# dio-pci.net
KiCad netlist of a schematic drawn in EAGLE
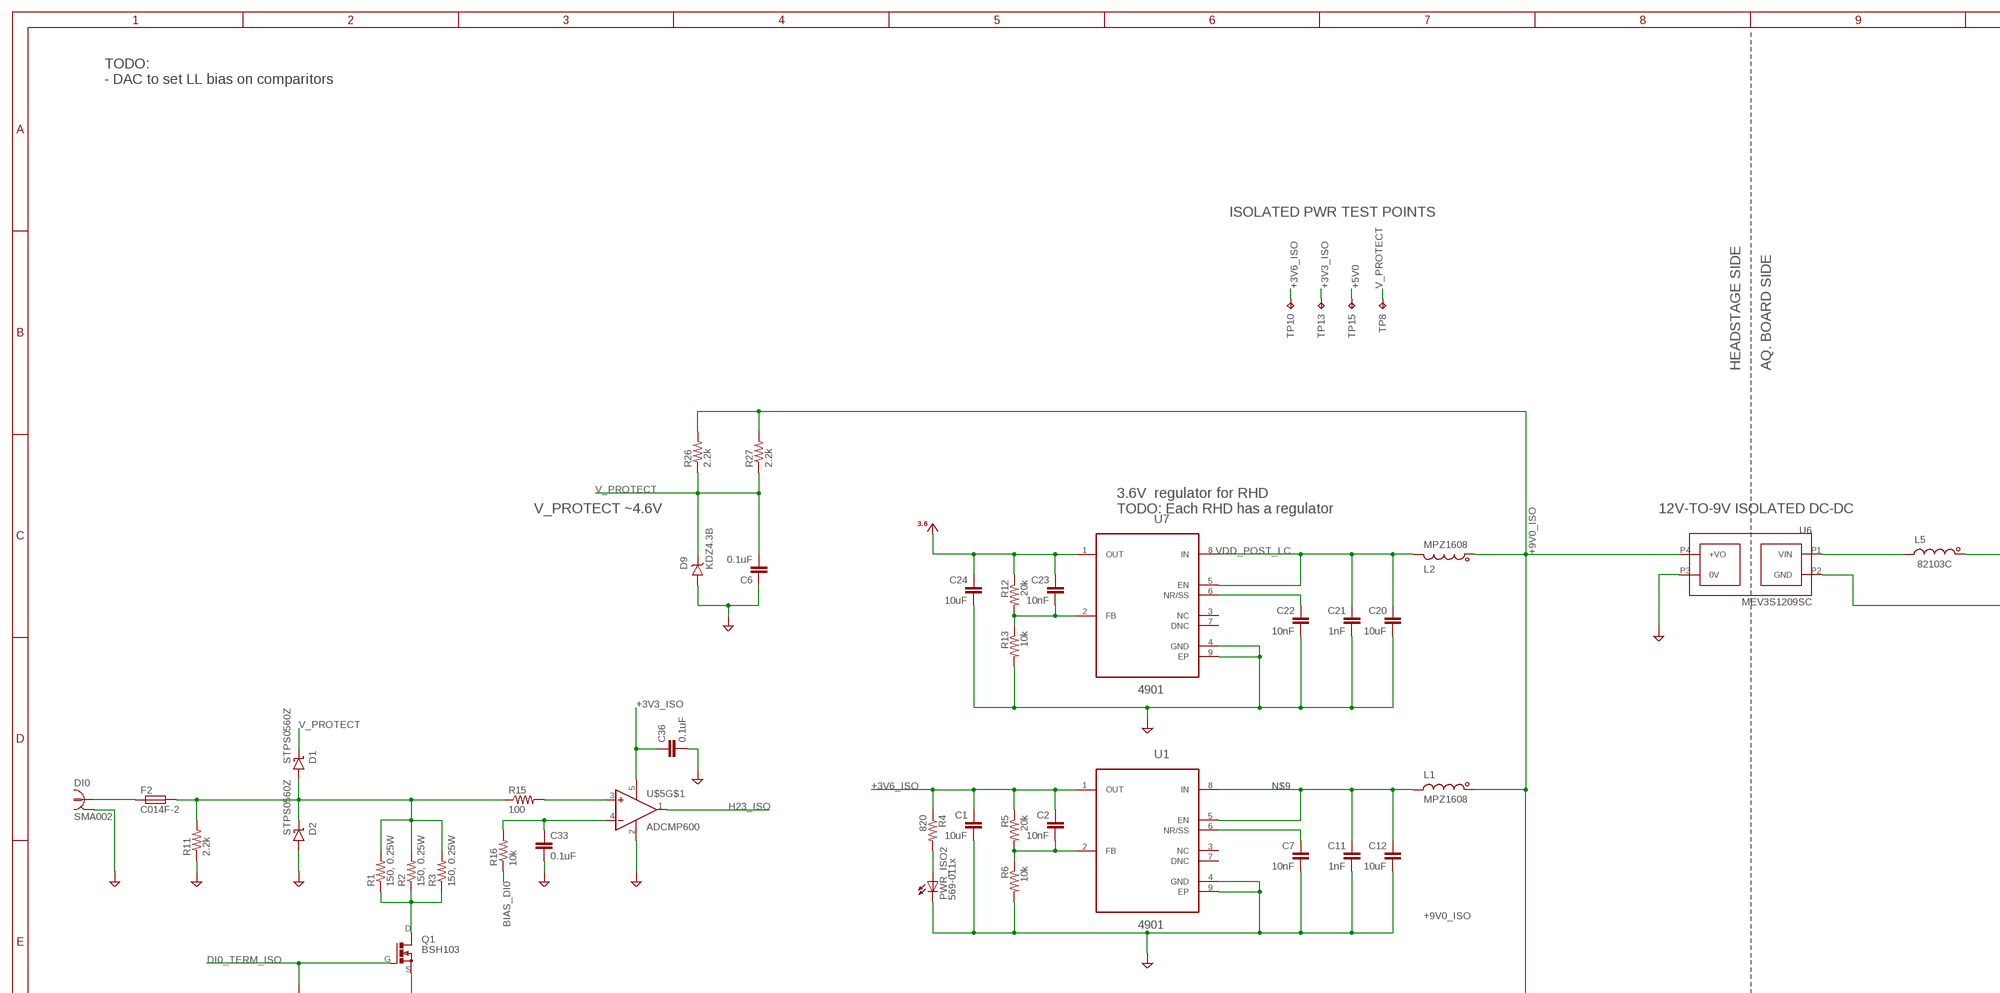
[diagram p0: schematic, sheet 1, part 1 of 3]
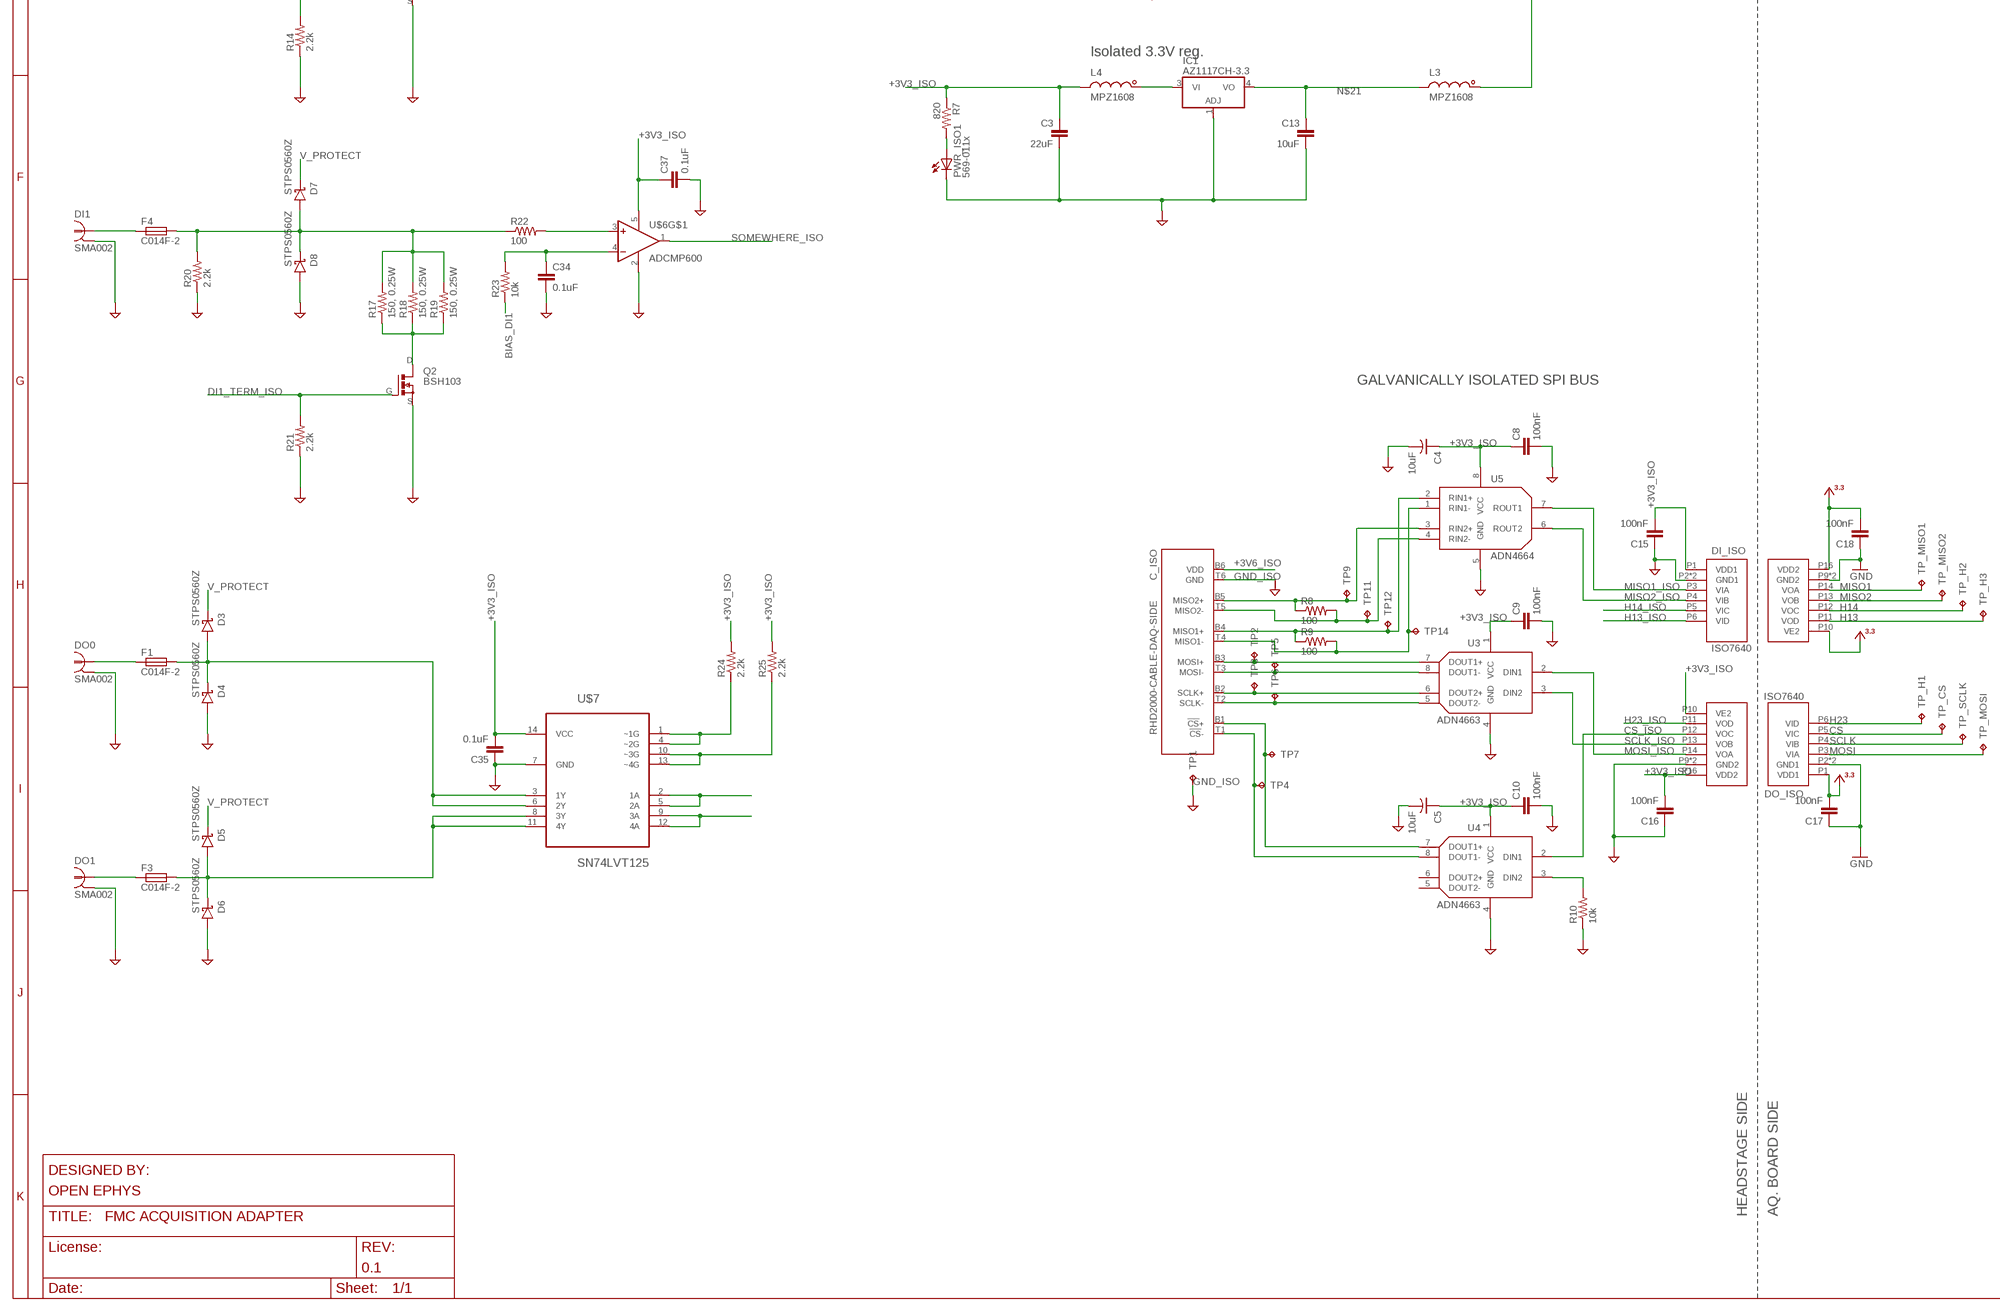
[diagram p1: schematic, sheet 1, part 2 of 3]
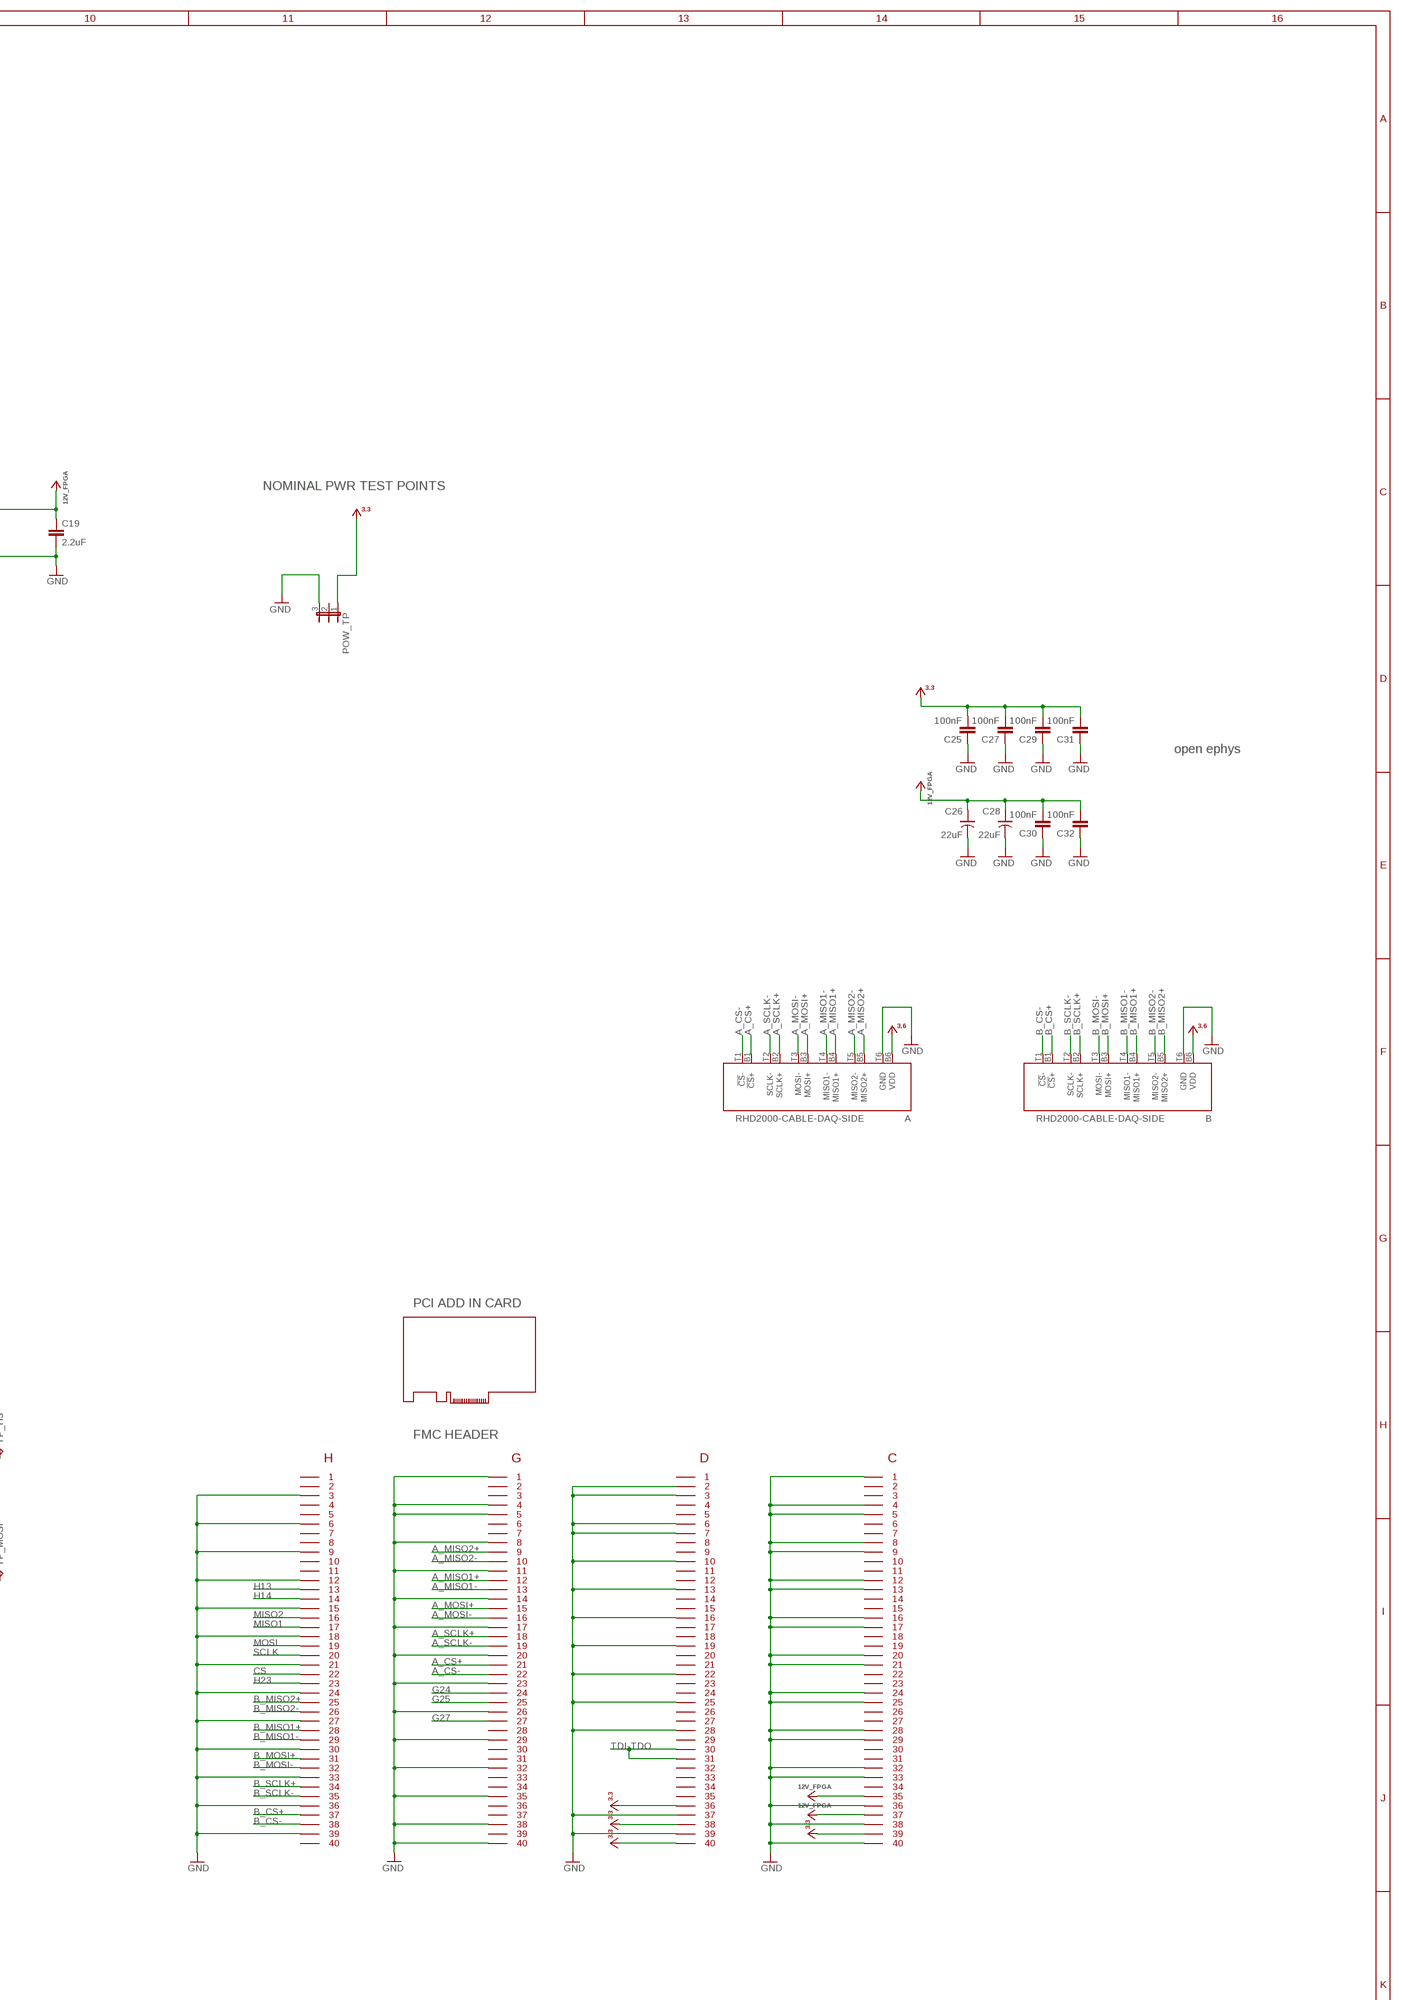
[diagram p2: schematic, sheet 1, part 3 of 3]

(export (version "E")
  (design (tool "Eeschema 10.0.6"))
  (components
    (comp (ref "A")
      (value "RHD2000-CABLE-DAQ-SIDE")
      (footprint "eagle-import:OMNETICS_PZN-12-AA")
      (libsource (lib "eagle-import") (part "RHD2000-CABLE-DAQ-SIDE"))
    )
    (comp (ref "B")
      (value "RHD2000-CABLE-DAQ-SIDE")
      (footprint "eagle-import:OMNETICS_PZN-12-AA")
      (libsource (lib "eagle-import") (part "RHD2000-CABLE-DAQ-SIDE"))
    )
    (comp (ref "C1")
      (value "10uF")
      (footprint "eagle-import:1206")
      (libsource (lib "eagle-import") (part "puggleboard_C_1206"))
    )
    (comp (ref "C2")
      (value "10nF")
      (footprint "eagle-import:0603")
      (libsource (lib "eagle-import") (part "jonnew_C_0603"))
    )
    (comp (ref "C3")
      (value "22uF")
      (footprint "eagle-import:1206")
      (libsource (lib "eagle-import") (part "C_1206"))
    )
    (comp (ref "C4")
      (value "10uF")
      (footprint "eagle-import:1206-POL")
      (libsource (lib "eagle-import") (part "C-POL_1206"))
    )
    (comp (ref "C5")
      (value "10uF")
      (footprint "eagle-import:1206-POL")
      (libsource (lib "eagle-import") (part "C-POL_1206"))
    )
    (comp (ref "C6")
      (value "0.1uF")
      (footprint "eagle-import:0603")
      (libsource (lib "eagle-import") (part "jonnew_C_0603"))
    )
    (comp (ref "C7")
      (value "10nF")
      (footprint "eagle-import:0603")
      (libsource (lib "eagle-import") (part "jonnew_C_0603"))
    )
    (comp (ref "C8")
      (value "100nF")
      (footprint "eagle-import:0603")
      (libsource (lib "eagle-import") (part "C_0603"))
    )
    (comp (ref "C9")
      (value "100nF")
      (footprint "eagle-import:0603")
      (libsource (lib "eagle-import") (part "C_0603"))
    )
    (comp (ref "C10")
      (value "100nF")
      (footprint "eagle-import:0603")
      (libsource (lib "eagle-import") (part "C_0603"))
    )
    (comp (ref "C11")
      (value "1nF")
      (footprint "eagle-import:0603")
      (libsource (lib "eagle-import") (part "jonnew_C_0603"))
    )
    (comp (ref "C12")
      (value "10uF")
      (footprint "eagle-import:1206")
      (libsource (lib "eagle-import") (part "puggleboard_C_1206"))
    )
    (comp (ref "C13")
      (value "10uF")
      (footprint "eagle-import:1206")
      (libsource (lib "eagle-import") (part "jonnew_C_1206"))
    )
    (comp (ref "C15")
      (value "100nF")
      (footprint "eagle-import:0603")
      (libsource (lib "eagle-import") (part "C_0603"))
    )
    (comp (ref "C16")
      (value "100nF")
      (footprint "eagle-import:0603")
      (libsource (lib "eagle-import") (part "C_0603"))
    )
    (comp (ref "C17")
      (value "100nF")
      (footprint "eagle-import:0603")
      (libsource (lib "eagle-import") (part "C_0603"))
    )
    (comp (ref "C18")
      (value "100nF")
      (footprint "eagle-import:0603")
      (libsource (lib "eagle-import") (part "C_0603"))
    )
    (comp (ref "C19")
      (value "2.2uF")
      (footprint "eagle-import:1206")
      (libsource (lib "eagle-import") (part "jonnew_C_1206"))
    )
    (comp (ref "C20")
      (value "10uF")
      (footprint "eagle-import:1206")
      (libsource (lib "eagle-import") (part "puggleboard_C_1206"))
    )
    (comp (ref "C21")
      (value "1nF")
      (footprint "eagle-import:0603")
      (libsource (lib "eagle-import") (part "jonnew_C_0603"))
    )
    (comp (ref "C22")
      (value "10nF")
      (footprint "eagle-import:0603")
      (libsource (lib "eagle-import") (part "jonnew_C_0603"))
    )
    (comp (ref "C23")
      (value "10nF")
      (footprint "eagle-import:0603")
      (libsource (lib "eagle-import") (part "jonnew_C_0603"))
    )
    (comp (ref "C24")
      (value "10uF")
      (footprint "eagle-import:1206")
      (libsource (lib "eagle-import") (part "puggleboard_C_1206"))
    )
    (comp (ref "C25")
      (value "100nF")
      (footprint "eagle-import:0603")
      (libsource (lib "eagle-import") (part "C_0603"))
    )
    (comp (ref "C26")
      (value "22uF")
      (footprint "eagle-import:1210-POL")
      (libsource (lib "eagle-import") (part "C-POL_1210"))
    )
    (comp (ref "C27")
      (value "100nF")
      (footprint "eagle-import:0603")
      (libsource (lib "eagle-import") (part "C_0603"))
    )
    (comp (ref "C28")
      (value "22uF")
      (footprint "eagle-import:1210-POL")
      (libsource (lib "eagle-import") (part "C-POL_1210"))
    )
    (comp (ref "C29")
      (value "100nF")
      (footprint "eagle-import:0603")
      (libsource (lib "eagle-import") (part "C_0603"))
    )
    (comp (ref "C30")
      (value "100nF")
      (footprint "eagle-import:0603")
      (libsource (lib "eagle-import") (part "C_0603"))
    )
    (comp (ref "C31")
      (value "100nF")
      (footprint "eagle-import:0603")
      (libsource (lib "eagle-import") (part "C_0603"))
    )
    (comp (ref "C32")
      (value "100nF")
      (footprint "eagle-import:0603")
      (libsource (lib "eagle-import") (part "C_0603"))
    )
    (comp (ref "C33")
      (value "0.1uF")
      (footprint "eagle-import:0603")
      (libsource (lib "eagle-import") (part "jonnew_C_0603"))
    )
    (comp (ref "C34")
      (value "0.1uF")
      (footprint "eagle-import:0603")
      (libsource (lib "eagle-import") (part "jonnew_C_0603"))
    )
    (comp (ref "C35")
      (value "0.1uF")
      (footprint "eagle-import:0603")
      (libsource (lib "eagle-import") (part "C_0603"))
    )
    (comp (ref "C36")
      (value "0.1uF")
      (footprint "eagle-import:0603")
      (libsource (lib "eagle-import") (part "jonnew_C_0603"))
    )
    (comp (ref "C37")
      (value "0.1uF")
      (footprint "eagle-import:0603")
      (libsource (lib "eagle-import") (part "jonnew_C_0603"))
    )
    (comp (ref "C_ISO")
      (value "RHD2000-CABLE-DAQ-SIDE")
      (footprint "eagle-import:OMNETICS_PZN-12-AA")
      (libsource (lib "eagle-import") (part "RHD2000-CABLE-DAQ-SIDE"))
    )
    (comp (ref "D1")
      (value "STPS0560Z")
      (footprint "eagle-import:SOD123")
      (libsource (lib "eagle-import") (part "S-DIODESOD-123"))
    )
    (comp (ref "D2")
      (value "STPS0560Z")
      (footprint "eagle-import:SOD123")
      (libsource (lib "eagle-import") (part "S-DIODESOD-123"))
    )
    (comp (ref "D3")
      (value "STPS0560Z")
      (footprint "eagle-import:SOD123")
      (libsource (lib "eagle-import") (part "S-DIODESOD-123"))
    )
    (comp (ref "D4")
      (value "STPS0560Z")
      (footprint "eagle-import:SOD123")
      (libsource (lib "eagle-import") (part "S-DIODESOD-123"))
    )
    (comp (ref "D5")
      (value "STPS0560Z")
      (footprint "eagle-import:SOD123")
      (libsource (lib "eagle-import") (part "S-DIODESOD-123"))
    )
    (comp (ref "D6")
      (value "STPS0560Z")
      (footprint "eagle-import:SOD123")
      (libsource (lib "eagle-import") (part "S-DIODESOD-123"))
    )
    (comp (ref "D7")
      (value "STPS0560Z")
      (footprint "eagle-import:SOD123")
      (libsource (lib "eagle-import") (part "S-DIODESOD-123"))
    )
    (comp (ref "D8")
      (value "STPS0560Z")
      (footprint "eagle-import:SOD123")
      (libsource (lib "eagle-import") (part "S-DIODESOD-123"))
    )
    (comp (ref "D9")
      (value "KDZ4.3B")
      (footprint "eagle-import:SOD123")
      (libsource (lib "eagle-import") (part "Z-DIODE_SOD123"))
    )
    (comp (ref "DI0")
      (value "SMA002")
      (footprint "eagle-import:SMA_JACK_CONREVSMA002-G")
      (libsource (lib "eagle-import") (part "COAX_CONREVSMA002-G"))
    )
    (comp (ref "DI1")
      (value "SMA002")
      (footprint "eagle-import:SMA_JACK_CONREVSMA002-G")
      (libsource (lib "eagle-import") (part "COAX_CONREVSMA002-G"))
    )
    (comp (ref "DI_ISO")
      (value "ISO7640")
      (footprint "eagle-import:SOIC_WIDE_16")
      (libsource (lib "eagle-import") (part "ADUM3440"))
    )
    (comp (ref "DO0")
      (value "SMA002")
      (footprint "eagle-import:SMA_JACK_CONREVSMA002-G")
      (libsource (lib "eagle-import") (part "COAX_CONREVSMA002-G"))
    )
    (comp (ref "DO1")
      (value "SMA002")
      (footprint "eagle-import:SMA_JACK_CONREVSMA002-G")
      (libsource (lib "eagle-import") (part "COAX_CONREVSMA002-G"))
    )
    (comp (ref "DO_ISO")
      (value "ISO7640")
      (footprint "eagle-import:SOIC_WIDE_16")
      (libsource (lib "eagle-import") (part "ADUM3440"))
    )
    (comp (ref "F1")
      (value "C014F-2")
      (footprint "eagle-import:1812")
      (libsource (lib "eagle-import") (part "FUSE_1812"))
    )
    (comp (ref "F2")
      (value "C014F-2")
      (footprint "eagle-import:1812")
      (libsource (lib "eagle-import") (part "FUSE_1812"))
    )
    (comp (ref "F3")
      (value "C014F-2")
      (footprint "eagle-import:1812")
      (libsource (lib "eagle-import") (part "FUSE_1812"))
    )
    (comp (ref "F4")
      (value "C014F-2")
      (footprint "eagle-import:1812")
      (libsource (lib "eagle-import") (part "FUSE_1812"))
    )
    (comp (ref "FMC")
      (value "FMC_LPC_160_PIN")
      (footprint "eagle-import:FMC_LPC_MALE_WITH_SP601_BSILK")
      (libsource (lib "eagle-import") (part "FMC_LPC_160_PIN"))
    )
    (comp (ref "IC1")
      (value "AZ1117CH-3.3")
      (footprint "eagle-import:SOT223")
      (libsource (lib "eagle-import") (part "317EMP"))
    )
    (comp (ref "L1")
      (value "MPZ1608")
      (footprint "eagle-import:0603")
      (libsource (lib "eagle-import") (part "L_0603"))
    )
    (comp (ref "L2")
      (value "MPZ1608")
      (footprint "eagle-import:0603")
      (libsource (lib "eagle-import") (part "L_0603"))
    )
    (comp (ref "L3")
      (value "MPZ1608")
      (footprint "eagle-import:0603")
      (libsource (lib "eagle-import") (part "L_0603"))
    )
    (comp (ref "L4")
      (value "MPZ1608")
      (footprint "eagle-import:0603")
      (libsource (lib "eagle-import") (part "L_0603"))
    )
    (comp (ref "L5")
      (value "82103C")
      (footprint "eagle-import:1210")
      (libsource (lib "eagle-import") (part "L_1210"))
    )
    (comp (ref "POW_TP")
      (value "JP3E")
      (footprint "eagle-import:JP3")
      (libsource (lib "eagle-import") (part "JP3E"))
    )
    (comp (ref "PWR_ISO")
      (value "569-011x")
      (footprint "eagle-import:569-011X-X00_LED_ARRAY")
      (libsource (lib "eagle-import") (part "LED_2X_VERTICAL"))
    )
    (comp (ref "Q1")
      (value "BSH103")
      (footprint "eagle-import:SOT23-GSD")
      (libsource (lib "eagle-import") (part "N-MOSFET_SOT23-GSD"))
    )
    (comp (ref "Q2")
      (value "BSH103")
      (footprint "eagle-import:SOT23-GSD")
      (libsource (lib "eagle-import") (part "N-MOSFET_SOT23-GSD"))
    )
    (comp (ref "R1")
      (value "150, 0.25W")
      (footprint "eagle-import:1206")
      (libsource (lib "eagle-import") (part "jonnew_R_1206"))
    )
    (comp (ref "R2")
      (value "150, 0.25W")
      (footprint "eagle-import:1206")
      (libsource (lib "eagle-import") (part "jonnew_R_1206"))
    )
    (comp (ref "R3")
      (value "150, 0.25W")
      (footprint "eagle-import:1206")
      (libsource (lib "eagle-import") (part "jonnew_R_1206"))
    )
    (comp (ref "R4")
      (value "820")
      (footprint "eagle-import:0603")
      (libsource (lib "eagle-import") (part "R_0603"))
    )
    (comp (ref "R5")
      (value "20k")
      (footprint "eagle-import:0603")
      (fields (field (name "MPN") "ERJ-3EKFxxxxV"))
      (libsource (lib "eagle-import") (part "jonnew_R_0603"))
    )
    (comp (ref "R6")
      (value "10k")
      (footprint "eagle-import:0603")
      (fields (field (name "MPN") "ERJ-3EKFxxxxV"))
      (libsource (lib "eagle-import") (part "jonnew_R_0603"))
    )
    (comp (ref "R7")
      (value "820")
      (footprint "eagle-import:0603")
      (libsource (lib "eagle-import") (part "R_0603"))
    )
    (comp (ref "R8")
      (value "100")
      (footprint "eagle-import:0603")
      (libsource (lib "eagle-import") (part "R_0603"))
    )
    (comp (ref "R9")
      (value "100")
      (footprint "eagle-import:0603")
      (libsource (lib "eagle-import") (part "R_0603"))
    )
    (comp (ref "R10")
      (value "10k")
      (footprint "eagle-import:0603")
      (fields (field (name "MPN") "ERJ-3EKFxxxxV"))
      (libsource (lib "eagle-import") (part "jonnew_R_0603"))
    )
    (comp (ref "R11")
      (value "2.2k")
      (footprint "eagle-import:0603")
      (fields (field (name "MPN") "ERJ-3EKFxxxxV"))
      (libsource (lib "eagle-import") (part "jonnew_R_0603"))
    )
    (comp (ref "R12")
      (value "20k")
      (footprint "eagle-import:0603")
      (fields (field (name "MPN") "ERJ-3EKFxxxxV"))
      (libsource (lib "eagle-import") (part "jonnew_R_0603"))
    )
    (comp (ref "R13")
      (value "10k")
      (footprint "eagle-import:0603")
      (fields (field (name "MPN") "ERJ-3EKFxxxxV"))
      (libsource (lib "eagle-import") (part "jonnew_R_0603"))
    )
    (comp (ref "R14")
      (value "2.2k")
      (footprint "eagle-import:0603")
      (fields (field (name "MPN") "ERJ-3EKFxxxxV"))
      (libsource (lib "eagle-import") (part "jonnew_R_0603"))
    )
    (comp (ref "R15")
      (value "100")
      (footprint "eagle-import:0603")
      (fields (field (name "MPN") "ERJ-3EKFxxxxV"))
      (libsource (lib "eagle-import") (part "jonnew_R_0603"))
    )
    (comp (ref "R16")
      (value "10k")
      (footprint "eagle-import:0603")
      (fields (field (name "MPN") "ERJ-3EKFxxxxV"))
      (libsource (lib "eagle-import") (part "jonnew_R_0603"))
    )
    (comp (ref "R17")
      (value "150, 0.25W")
      (footprint "eagle-import:1206")
      (libsource (lib "eagle-import") (part "jonnew_R_1206"))
    )
    (comp (ref "R18")
      (value "150, 0.25W")
      (footprint "eagle-import:1206")
      (libsource (lib "eagle-import") (part "jonnew_R_1206"))
    )
    (comp (ref "R19")
      (value "150, 0.25W")
      (footprint "eagle-import:1206")
      (libsource (lib "eagle-import") (part "jonnew_R_1206"))
    )
    (comp (ref "R20")
      (value "2.2k")
      (footprint "eagle-import:0603")
      (fields (field (name "MPN") "ERJ-3EKFxxxxV"))
      (libsource (lib "eagle-import") (part "jonnew_R_0603"))
    )
    (comp (ref "R21")
      (value "2.2k")
      (footprint "eagle-import:0603")
      (fields (field (name "MPN") "ERJ-3EKFxxxxV"))
      (libsource (lib "eagle-import") (part "jonnew_R_0603"))
    )
    (comp (ref "R22")
      (value "100")
      (footprint "eagle-import:0603")
      (fields (field (name "MPN") "ERJ-3EKFxxxxV"))
      (libsource (lib "eagle-import") (part "jonnew_R_0603"))
    )
    (comp (ref "R23")
      (value "10k")
      (footprint "eagle-import:0603")
      (fields (field (name "MPN") "ERJ-3EKFxxxxV"))
      (libsource (lib "eagle-import") (part "jonnew_R_0603"))
    )
    (comp (ref "R24")
      (value "2.2k")
      (footprint "eagle-import:0603")
      (fields (field (name "MPN") "ERJ-3EKFxxxxV"))
      (libsource (lib "eagle-import") (part "jonnew_R_0603"))
    )
    (comp (ref "R25")
      (value "2.2k")
      (footprint "eagle-import:0603")
      (fields (field (name "MPN") "ERJ-3EKFxxxxV"))
      (libsource (lib "eagle-import") (part "jonnew_R_0603"))
    )
    (comp (ref "R26")
      (value "2.2k")
      (footprint "eagle-import:0603")
      (fields (field (name "MPN") "ERJ-3EKFxxxxV"))
      (libsource (lib "eagle-import") (part "jonnew_R_0603"))
    )
    (comp (ref "R27")
      (value "2.2k")
      (footprint "eagle-import:0603")
      (fields (field (name "MPN") "ERJ-3EKFxxxxV"))
      (libsource (lib "eagle-import") (part "jonnew_R_0603"))
    )
    (comp (ref "TP1")
      (value "GND-ISO")
      (footprint "eagle-import:P1-13")
      (libsource (lib "eagle-import") (part "TPPAD1-13"))
    )
    (comp (ref "TP2")
      (value "MOSI+")
      (footprint "eagle-import:TP06R")
      (libsource (lib "eagle-import") (part "TPTP06R"))
    )
    (comp (ref "TP3")
      (value "SCLK+")
      (footprint "eagle-import:TP06R")
      (libsource (lib "eagle-import") (part "TPTP06R"))
    )
    (comp (ref "TP4")
      (value "CS-")
      (footprint "eagle-import:TP06R")
      (libsource (lib "eagle-import") (part "TPTP06R"))
    )
    (comp (ref "TP5")
      (value "MOSI-")
      (footprint "eagle-import:TP06R")
      (libsource (lib "eagle-import") (part "TPTP06R"))
    )
    (comp (ref "TP6")
      (value "SCLK-")
      (footprint "eagle-import:TP06R")
      (libsource (lib "eagle-import") (part "TPTP06R"))
    )
    (comp (ref "TP7")
      (value "CS+")
      (footprint "eagle-import:TP06R")
      (libsource (lib "eagle-import") (part "TPTP06R"))
    )
    (comp (ref "TP8")
      (value "+5V0")
      (footprint "eagle-import:TP06R")
      (libsource (lib "eagle-import") (part "TPTP06R"))
    )
    (comp (ref "TP9")
      (value "MISO2+")
      (footprint "eagle-import:TP06R")
      (libsource (lib "eagle-import") (part "TPTP06R"))
    )
    (comp (ref "TP10")
      (value "+3V6")
      (footprint "eagle-import:TP06R")
      (libsource (lib "eagle-import") (part "TPTP06R"))
    )
    (comp (ref "TP11")
      (value "MISO2-")
      (footprint "eagle-import:TP06R")
      (libsource (lib "eagle-import") (part "TPTP06R"))
    )
    (comp (ref "TP12")
      (value "MISO1+")
      (footprint "eagle-import:TP06R")
      (libsource (lib "eagle-import") (part "TPTP06R"))
    )
    (comp (ref "TP13")
      (value "+3V3")
      (footprint "eagle-import:TP06R")
      (libsource (lib "eagle-import") (part "TPTP06R"))
    )
    (comp (ref "TP14")
      (value "MISO1-")
      (footprint "eagle-import:TP06R")
      (libsource (lib "eagle-import") (part "TPTP06R"))
    )
    (comp (ref "TP15")
      (value "+5V0")
      (footprint "eagle-import:TP06R")
      (libsource (lib "eagle-import") (part "TPTP06R"))
    )
    (comp (ref "TP_CS")
      (value "CS")
      (footprint "eagle-import:TP06R")
      (libsource (lib "eagle-import") (part "TPTP06R"))
    )
    (comp (ref "TP_H1")
      (value "H23")
      (footprint "eagle-import:TP06R")
      (libsource (lib "eagle-import") (part "TPTP06R"))
    )
    (comp (ref "TP_H2")
      (value "H14")
      (footprint "eagle-import:TP06R")
      (libsource (lib "eagle-import") (part "TPTP06R"))
    )
    (comp (ref "TP_H3")
      (value "H13")
      (footprint "eagle-import:TP06R")
      (libsource (lib "eagle-import") (part "TPTP06R"))
    )
    (comp (ref "TP_MISO1")
      (value "MISO1")
      (footprint "eagle-import:TP06R")
      (libsource (lib "eagle-import") (part "TPTP06R"))
    )
    (comp (ref "TP_MISO2")
      (value "MISO2")
      (footprint "eagle-import:TP06R")
      (libsource (lib "eagle-import") (part "TPTP06R"))
    )
    (comp (ref "TP_MOSI")
      (value "MOSI")
      (footprint "eagle-import:TP06R")
      (libsource (lib "eagle-import") (part "TPTP06R"))
    )
    (comp (ref "TP_SCLK")
      (value "SCLK")
      (footprint "eagle-import:TP06R")
      (libsource (lib "eagle-import") (part "TPTP06R"))
    )
    (comp (ref "U$1")
      (value "OPEN_EPHYS_LOGO")
      (footprint "eagle-import:OPEN_EPHYS_LOGO")
      (libsource (lib "eagle-import") (part "OPEN_EPHYS_LOGO"))
    )
    (comp (ref "U$2")
      (value "PCI-MECH_STD-H_HALF-W")
      (footprint "eagle-import:PCI-ADDIN_STD-H_HALF-L")
      (libsource (lib "eagle-import") (part "PCI-MECH_STD-H_HALF-W"))
    )
    (comp (ref "U$5")
      (value "ADCMP600")
      (footprint "eagle-import:SOT-23-5")
      (libsource (lib "eagle-import") (part "COMPARITOR_ADCMP600"))
    )
    (comp (ref "U$6")
      (value "ADCMP600")
      (footprint "eagle-import:SOT-23-5")
      (libsource (lib "eagle-import") (part "COMPARITOR_ADCMP600"))
    )
    (comp (ref "U$7")
      (value "SN74LVT125")
      (footprint "eagle-import:SO14")
      (libsource (lib "eagle-import") (part "QUAD-LINE-DRIVER_SOIC"))
    )
    (comp (ref "U1")
      (value "4901")
      (footprint "eagle-import:SOP65P490X110-9N")
      (fields (field (name "MPN") "TPS7A4901DGNR"))
      (libsource (lib "eagle-import") (part "TPS7A4901DGNR"))
    )
    (comp (ref "U3")
      (value "ADN4663")
      (footprint "eagle-import:SOIC127P500X400-8N")
      (libsource (lib "eagle-import") (part "ADN4663_SOIC"))
    )
    (comp (ref "U4")
      (value "ADN4663")
      (footprint "eagle-import:SOIC127P500X400-8N")
      (libsource (lib "eagle-import") (part "ADN4663_SOIC"))
    )
    (comp (ref "U5")
      (value "ADN4664")
      (footprint "eagle-import:SOIC127P500X400-8N")
      (libsource (lib "eagle-import") (part "ADN4664_SOIC"))
    )
    (comp (ref "U6")
      (value "MEV3S1209SC")
      (footprint "eagle-import:MEV3")
      (libsource (lib "eagle-import") (part "DC-DC-CONVERTER_MEV3"))
    )
    (comp (ref "U7")
      (value "4901")
      (footprint "eagle-import:SOP65P490X110-9N")
      (fields (field (name "MPN") "TPS7A4901DGNR"))
      (libsource (lib "eagle-import") (part "TPS7A4901DGNR"))
    )
  )
  (nets
    (net (code "1") (name "+3V3") (class "Default")
      (node (ref "C17") (pin "2") (pinfunction "2_2") (pintype "passive"))
      (node (ref "C18") (pin "2") (pinfunction "2_2") (pintype "passive"))
      (node (ref "C25") (pin "2") (pinfunction "2_2") (pintype "passive"))
      (node (ref "C27") (pin "2") (pinfunction "2_2") (pintype "passive"))
      (node (ref "C29") (pin "2") (pinfunction "2_2") (pintype "passive"))
      (node (ref "C31") (pin "2") (pinfunction "2_2") (pintype "passive"))
      (node (ref "DI_ISO") (pin "P10") (pinfunction "VE2_P10") (pintype "bidirectional"))
      (node (ref "DI_ISO") (pin "P16") (pinfunction "VDD2_P16") (pintype "bidirectional"))
      (node (ref "DO_ISO") (pin "P1") (pinfunction "VDD1_P1") (pintype "bidirectional"))
      (node (ref "FMC") (pin "P$116") (pinfunction "P$116_P$116") (pintype "bidirectional"))
      (node (ref "FMC") (pin "P$118") (pinfunction "P$118_P$118") (pintype "bidirectional"))
      (node (ref "FMC") (pin "P$120") (pinfunction "P$120_P$120") (pintype "bidirectional"))
      (node (ref "FMC") (pin "P$159") (pinfunction "P$159_P$159") (pintype "bidirectional"))
      (node (ref "POW_TP") (pin "1") (pinfunction "1_1") (pintype "passive"))
    )
    (net (code "2") (name "+3V6") (class "Default")
      (node (ref "A") (pin "B6") (pinfunction "VDD_B6") (pintype "bidirectional"))
      (node (ref "B") (pin "B6") (pinfunction "VDD_B6") (pintype "bidirectional"))
      (node (ref "C23") (pin "1") (pinfunction "1_1") (pintype "passive"))
      (node (ref "C24") (pin "1") (pinfunction "1_1") (pintype "passive"))
      (node (ref "R12") (pin "1") (pinfunction "1_1") (pintype "passive"))
      (node (ref "U7") (pin "1") (pinfunction "OUT_1") (pintype "passive"))
    )
    (net (code "3") (name "/+3V3_ISO") (class "Default")
      (node (ref "C10") (pin "1") (pinfunction "1_1") (pintype "passive"))
      (node (ref "C15") (pin "2") (pinfunction "2_2") (pintype "passive"))
      (node (ref "C16") (pin "2") (pinfunction "2_2") (pintype "passive"))
      (node (ref "C3") (pin "1") (pinfunction "1_1") (pintype "passive"))
      (node (ref "C35") (pin "2") (pinfunction "2_2") (pintype "passive"))
      (node (ref "C36") (pin "1") (pinfunction "1_1") (pintype "passive"))
      (node (ref "C37") (pin "1") (pinfunction "1_1") (pintype "passive"))
      (node (ref "C4") (pin "+") (pinfunction "+_+") (pintype "passive"))
      (node (ref "C5") (pin "+") (pinfunction "+_+") (pintype "passive"))
      (node (ref "C8") (pin "1") (pinfunction "1_1") (pintype "passive"))
      (node (ref "C9") (pin "1") (pinfunction "1_1") (pintype "passive"))
      (node (ref "DI_ISO") (pin "P1") (pinfunction "VDD1_P1") (pintype "bidirectional"))
      (node (ref "DO_ISO") (pin "P10") (pinfunction "VE2_P10") (pintype "bidirectional"))
      (node (ref "DO_ISO") (pin "P16") (pinfunction "VDD2_P16") (pintype "bidirectional"))
      (node (ref "L4") (pin "2") (pinfunction "2_2") (pintype "passive"))
      (node (ref "R24") (pin "2") (pinfunction "2_2") (pintype "passive"))
      (node (ref "R25") (pin "2") (pinfunction "2_2") (pintype "passive"))
      (node (ref "R7") (pin "1") (pinfunction "1_1") (pintype "passive"))
      (node (ref "TP13") (pin "TP") (pinfunction "TP_TP") (pintype "input"))
      (node (ref "U$5") (pin "5") (pinfunction "V+_5") (pintype "power_in"))
      (node (ref "U$6") (pin "5") (pinfunction "V+_5") (pintype "power_in"))
      (node (ref "U$7") (pin "14") (pinfunction "VCC_14") (pintype "passive"))
      (node (ref "U3") (pin "1") (pinfunction "VCC_1") (pintype "bidirectional"))
      (node (ref "U4") (pin "1") (pinfunction "VCC_1") (pintype "bidirectional"))
      (node (ref "U5") (pin "8") (pinfunction "VCC_8") (pintype "bidirectional"))
    )
    (net (code "4") (name "/+3V6_ISO") (class "Default")
      (node (ref "C1") (pin "1") (pinfunction "1_1") (pintype "passive"))
      (node (ref "C2") (pin "1") (pinfunction "1_1") (pintype "passive"))
      (node (ref "C_ISO") (pin "B6") (pinfunction "VDD_B6") (pintype "bidirectional"))
      (node (ref "R4") (pin "1") (pinfunction "1_1") (pintype "passive"))
      (node (ref "R5") (pin "1") (pinfunction "1_1") (pintype "passive"))
      (node (ref "TP10") (pin "TP") (pinfunction "TP_TP") (pintype "input"))
      (node (ref "U1") (pin "1") (pinfunction "OUT_1") (pintype "passive"))
    )
    (net (code "5") (name "/+5V0") (class "Default")
      (node (ref "TP15") (pin "TP") (pinfunction "TP_TP") (pintype "input"))
    )
    (net (code "6") (name "/+9V0_ISO") (class "Default")
      (node (ref "L1") (pin "1") (pinfunction "1_1") (pintype "passive"))
      (node (ref "L2") (pin "1") (pinfunction "1_1") (pintype "passive"))
      (node (ref "L3") (pin "1") (pinfunction "1_1") (pintype "passive"))
      (node (ref "R26") (pin "2") (pinfunction "2_2") (pintype "passive"))
      (node (ref "R27") (pin "2") (pinfunction "2_2") (pintype "passive"))
      (node (ref "U6") (pin "P4") (pinfunction "+VO_P4") (pintype "bidirectional"))
    )
    (net (code "7") (name "/12V_FPGA") (class "Default")
      (node (ref "C19") (pin "1") (pinfunction "1_1") (pintype "passive"))
      (node (ref "C26") (pin "+") (pinfunction "+_+") (pintype "passive"))
      (node (ref "C28") (pin "+") (pinfunction "+_+") (pintype "passive"))
      (node (ref "C30") (pin "2") (pinfunction "2_2") (pintype "passive"))
      (node (ref "C32") (pin "2") (pinfunction "2_2") (pintype "passive"))
      (node (ref "FMC") (pin "P$155") (pinfunction "P$155_P$155") (pintype "bidirectional"))
      (node (ref "FMC") (pin "P$157") (pinfunction "P$157_P$157") (pintype "bidirectional"))
      (node (ref "L5") (pin "1") (pinfunction "1_1") (pintype "passive"))
    )
    (net (code "8") (name "/A_CS+") (class "Default")
      (node (ref "A") (pin "B1") (pinfunction "~{CS}+_B1") (pintype "bidirectional"))
      (node (ref "FMC") (pin "P$61") (pinfunction "P$61_P$61") (pintype "bidirectional"))
    )
    (net (code "9") (name "/A_CS-") (class "Default")
      (node (ref "A") (pin "T1") (pinfunction "~{CS}-_T1") (pintype "bidirectional"))
      (node (ref "FMC") (pin "P$62") (pinfunction "P$62_P$62") (pintype "bidirectional"))
    )
    (net (code "10") (name "/A_MISO1+") (class "Default")
      (node (ref "A") (pin "B4") (pinfunction "MISO1+_B4") (pintype "bidirectional"))
      (node (ref "FMC") (pin "P$52") (pinfunction "P$52_P$52") (pintype "bidirectional"))
    )
    (net (code "11") (name "/A_MISO1-") (class "Default")
      (node (ref "A") (pin "T4") (pinfunction "MISO1-_T4") (pintype "bidirectional"))
      (node (ref "FMC") (pin "P$53") (pinfunction "P$53_P$53") (pintype "bidirectional"))
    )
    (net (code "12") (name "/A_MISO2+") (class "Default")
      (node (ref "A") (pin "B5") (pinfunction "MISO2+_B5") (pintype "bidirectional"))
      (node (ref "FMC") (pin "P$49") (pinfunction "P$49_P$49") (pintype "bidirectional"))
    )
    (net (code "13") (name "/A_MISO2-") (class "Default")
      (node (ref "A") (pin "T5") (pinfunction "MISO2-_T5") (pintype "bidirectional"))
      (node (ref "FMC") (pin "P$50") (pinfunction "P$50_P$50") (pintype "bidirectional"))
    )
    (net (code "14") (name "/A_MOSI+") (class "Default")
      (node (ref "A") (pin "B3") (pinfunction "MOSI+_B3") (pintype "bidirectional"))
      (node (ref "FMC") (pin "P$55") (pinfunction "P$55_P$55") (pintype "bidirectional"))
    )
    (net (code "15") (name "/A_MOSI-") (class "Default")
      (node (ref "A") (pin "T3") (pinfunction "MOSI-_T3") (pintype "bidirectional"))
      (node (ref "FMC") (pin "P$56") (pinfunction "P$56_P$56") (pintype "bidirectional"))
    )
    (net (code "16") (name "/A_SCLK+") (class "Default")
      (node (ref "A") (pin "B2") (pinfunction "SCLK+_B2") (pintype "bidirectional"))
      (node (ref "FMC") (pin "P$58") (pinfunction "P$58_P$58") (pintype "bidirectional"))
    )
    (net (code "17") (name "/A_SCLK-") (class "Default")
      (node (ref "A") (pin "T2") (pinfunction "SCLK-_T2") (pintype "bidirectional"))
      (node (ref "FMC") (pin "P$59") (pinfunction "P$59_P$59") (pintype "bidirectional"))
    )
    (net (code "18") (name "/BIAS_DI0") (class "Default")
      (node (ref "R16") (pin "1") (pinfunction "1_1") (pintype "passive"))
    )
    (net (code "19") (name "/BIAS_DI1") (class "Default")
      (node (ref "R23") (pin "1") (pinfunction "1_1") (pintype "passive"))
    )
    (net (code "20") (name "/B_CS+") (class "Default")
      (node (ref "B") (pin "B1") (pinfunction "~{CS}+_B1") (pintype "bidirectional"))
      (node (ref "FMC") (pin "P$37") (pinfunction "P$37_P$37") (pintype "bidirectional"))
    )
    (net (code "21") (name "/B_CS-") (class "Default")
      (node (ref "B") (pin "T1") (pinfunction "~{CS}-_T1") (pintype "bidirectional"))
      (node (ref "FMC") (pin "P$38") (pinfunction "P$38_P$38") (pintype "bidirectional"))
    )
    (net (code "22") (name "/B_MISO1+") (class "Default")
      (node (ref "B") (pin "B4") (pinfunction "MISO1+_B4") (pintype "bidirectional"))
      (node (ref "FMC") (pin "P$28") (pinfunction "P$28_P$28") (pintype "bidirectional"))
    )
    (net (code "23") (name "/B_MISO1-") (class "Default")
      (node (ref "B") (pin "T4") (pinfunction "MISO1-_T4") (pintype "bidirectional"))
      (node (ref "FMC") (pin "P$29") (pinfunction "P$29_P$29") (pintype "bidirectional"))
    )
    (net (code "24") (name "/B_MISO2+") (class "Default")
      (node (ref "B") (pin "B5") (pinfunction "MISO2+_B5") (pintype "bidirectional"))
      (node (ref "FMC") (pin "P$25") (pinfunction "P$25_P$25") (pintype "bidirectional"))
    )
    (net (code "25") (name "/B_MISO2-") (class "Default")
      (node (ref "B") (pin "T5") (pinfunction "MISO2-_T5") (pintype "bidirectional"))
      (node (ref "FMC") (pin "P$26") (pinfunction "P$26_P$26") (pintype "bidirectional"))
    )
    (net (code "26") (name "/B_MOSI+") (class "Default")
      (node (ref "B") (pin "B3") (pinfunction "MOSI+_B3") (pintype "bidirectional"))
      (node (ref "FMC") (pin "P$31") (pinfunction "P$31_P$31") (pintype "bidirectional"))
    )
    (net (code "27") (name "/B_MOSI-") (class "Default")
      (node (ref "B") (pin "T3") (pinfunction "MOSI-_T3") (pintype "bidirectional"))
      (node (ref "FMC") (pin "P$32") (pinfunction "P$32_P$32") (pintype "bidirectional"))
    )
    (net (code "28") (name "/B_SCLK+") (class "Default")
      (node (ref "B") (pin "B2") (pinfunction "SCLK+_B2") (pintype "bidirectional"))
      (node (ref "FMC") (pin "P$34") (pinfunction "P$34_P$34") (pintype "bidirectional"))
    )
    (net (code "29") (name "/B_SCLK-") (class "Default")
      (node (ref "B") (pin "T2") (pinfunction "SCLK-_T2") (pintype "bidirectional"))
      (node (ref "FMC") (pin "P$35") (pinfunction "P$35_P$35") (pintype "bidirectional"))
    )
    (net (code "30") (name "/CS") (class "Default")
      (node (ref "DO_ISO") (pin "P5") (pinfunction "VIC_P5") (pintype "bidirectional"))
      (node (ref "FMC") (pin "P$22") (pinfunction "P$22_P$22") (pintype "bidirectional"))
      (node (ref "TP_CS") (pin "TP") (pinfunction "TP_TP") (pintype "input"))
    )
    (net (code "31") (name "/CS_ISO") (class "Default")
      (node (ref "DO_ISO") (pin "P12") (pinfunction "VOC_P12") (pintype "bidirectional"))
      (node (ref "U4") (pin "2") (pinfunction "DIN1_2") (pintype "bidirectional"))
    )
    (net (code "32") (name "/DI0_TERM_ISO") (class "Default")
      (node (ref "Q1") (pin "G") (pinfunction "G_G") (pintype "bidirectional"))
      (node (ref "R14") (pin "2") (pinfunction "2_2") (pintype "passive"))
    )
    (net (code "33") (name "/DI1_TERM_ISO") (class "Default")
      (node (ref "Q2") (pin "G") (pinfunction "G_G") (pintype "bidirectional"))
      (node (ref "R21") (pin "2") (pinfunction "2_2") (pintype "passive"))
    )
    (net (code "34") (name "/G24") (class "Default")
      (node (ref "FMC") (pin "P$64") (pinfunction "P$64_P$64") (pintype "bidirectional"))
    )
    (net (code "35") (name "/G25") (class "Default")
      (node (ref "FMC") (pin "P$65") (pinfunction "P$65_P$65") (pintype "bidirectional"))
    )
    (net (code "36") (name "/G27") (class "Default")
      (node (ref "FMC") (pin "P$67") (pinfunction "P$67_P$67") (pintype "bidirectional"))
    )
    (net (code "37") (name "/H13") (class "Default")
      (node (ref "DI_ISO") (pin "P11") (pinfunction "VOD_P11") (pintype "bidirectional"))
      (node (ref "FMC") (pin "P$13") (pinfunction "P$13_P$13") (pintype "bidirectional"))
      (node (ref "TP_H3") (pin "TP") (pinfunction "TP_TP") (pintype "input"))
    )
    (net (code "38") (name "/H13_ISO") (class "Default")
      (node (ref "DI_ISO") (pin "P6") (pinfunction "VID_P6") (pintype "bidirectional"))
      (node (ref "U$7") (pin "12") (pinfunction "4A_12") (pintype "input"))
      (node (ref "U$7") (pin "9") (pinfunction "3A_9") (pintype "input"))
    )
    (net (code "39") (name "/H14") (class "Default")
      (node (ref "DI_ISO") (pin "P12") (pinfunction "VOC_P12") (pintype "bidirectional"))
      (node (ref "FMC") (pin "P$14") (pinfunction "P$14_P$14") (pintype "bidirectional"))
      (node (ref "TP_H2") (pin "TP") (pinfunction "TP_TP") (pintype "input"))
    )
    (net (code "40") (name "/H14_ISO") (class "Default")
      (node (ref "DI_ISO") (pin "P5") (pinfunction "VIC_P5") (pintype "bidirectional"))
      (node (ref "U$7") (pin "2") (pinfunction "1A_2") (pintype "input"))
      (node (ref "U$7") (pin "5") (pinfunction "2A_5") (pintype "input"))
    )
    (net (code "41") (name "/H23") (class "Default")
      (node (ref "DO_ISO") (pin "P6") (pinfunction "VID_P6") (pintype "bidirectional"))
      (node (ref "FMC") (pin "P$23") (pinfunction "P$23_P$23") (pintype "bidirectional"))
      (node (ref "TP_H1") (pin "TP") (pinfunction "TP_TP") (pintype "input"))
    )
    (net (code "42") (name "/H23_ISO") (class "Default")
      (node (ref "DO_ISO") (pin "P11") (pinfunction "VOD_P11") (pintype "bidirectional"))
      (node (ref "U$5") (pin "1") (pinfunction "OUT_1") (pintype "output"))
    )
    (net (code "43") (name "/MISO1") (class "Default")
      (node (ref "DI_ISO") (pin "P14") (pinfunction "VOA_P14") (pintype "bidirectional"))
      (node (ref "FMC") (pin "P$17") (pinfunction "P$17_P$17") (pintype "bidirectional"))
      (node (ref "TP_MISO1") (pin "TP") (pinfunction "TP_TP") (pintype "input"))
    )
    (net (code "44") (name "/MISO1_ISO") (class "Default")
      (node (ref "DI_ISO") (pin "P3") (pinfunction "VIA_P3") (pintype "bidirectional"))
      (node (ref "U5") (pin "7") (pinfunction "ROUT1_7") (pintype "bidirectional"))
    )
    (net (code "45") (name "/MISO2") (class "Default")
      (node (ref "DI_ISO") (pin "P13") (pinfunction "VOB_P13") (pintype "bidirectional"))
      (node (ref "FMC") (pin "P$16") (pinfunction "P$16_P$16") (pintype "bidirectional"))
      (node (ref "TP_MISO2") (pin "TP") (pinfunction "TP_TP") (pintype "input"))
    )
    (net (code "46") (name "/MISO2_ISO") (class "Default")
      (node (ref "DI_ISO") (pin "P4") (pinfunction "VIB_P4") (pintype "bidirectional"))
      (node (ref "U5") (pin "6") (pinfunction "ROUT2_6") (pintype "bidirectional"))
    )
    (net (code "47") (name "/MOSI") (class "Default")
      (node (ref "DO_ISO") (pin "P3") (pinfunction "VIA_P3") (pintype "bidirectional"))
      (node (ref "FMC") (pin "P$19") (pinfunction "P$19_P$19") (pintype "bidirectional"))
      (node (ref "TP_MOSI") (pin "TP") (pinfunction "TP_TP") (pintype "input"))
    )
    (net (code "48") (name "/MOSI_ISO") (class "Default")
      (node (ref "DO_ISO") (pin "P14") (pinfunction "VOA_P14") (pintype "bidirectional"))
      (node (ref "U3") (pin "2") (pinfunction "DIN1_2") (pintype "bidirectional"))
    )
    (net (code "49") (name "/N$9") (class "Default")
      (node (ref "C11") (pin "1") (pinfunction "1_1") (pintype "passive"))
      (node (ref "C12") (pin "1") (pinfunction "1_1") (pintype "passive"))
      (node (ref "L1") (pin "2") (pinfunction "2_2") (pintype "passive"))
      (node (ref "U1") (pin "5") (pinfunction "EN_5") (pintype "input"))
      (node (ref "U1") (pin "8") (pinfunction "IN_8") (pintype "passive"))
    )
    (net (code "50") (name "/N$21") (class "Default")
      (node (ref "C13") (pin "1") (pinfunction "1_1") (pintype "passive"))
      (node (ref "IC1") (pin "4") (pinfunction "VO_4") (pintype "passive"))
      (node (ref "L3") (pin "2") (pinfunction "2_2") (pintype "passive"))
    )
    (net (code "51") (name "/SCLK") (class "Default")
      (node (ref "DO_ISO") (pin "P4") (pinfunction "VIB_P4") (pintype "bidirectional"))
      (node (ref "FMC") (pin "P$20") (pinfunction "P$20_P$20") (pintype "bidirectional"))
      (node (ref "TP_SCLK") (pin "TP") (pinfunction "TP_TP") (pintype "input"))
    )
    (net (code "52") (name "/SCLK_ISO") (class "Default")
      (node (ref "DO_ISO") (pin "P13") (pinfunction "VOB_P13") (pintype "bidirectional"))
      (node (ref "U3") (pin "3") (pinfunction "DIN2_3") (pintype "bidirectional"))
    )
    (net (code "53") (name "/SOMEWHERE_ISO") (class "Default")
      (node (ref "U$6") (pin "1") (pinfunction "OUT_1") (pintype "output"))
    )
    (net (code "54") (name "/TDI-TDO") (class "Default")
      (node (ref "FMC") (pin "P$110") (pinfunction "P$110_P$110") (pintype "bidirectional"))
      (node (ref "FMC") (pin "P$111") (pinfunction "P$111_P$111") (pintype "bidirectional"))
    )
    (net (code "55") (name "/VDD_POST_LC") (class "Default")
      (node (ref "C20") (pin "1") (pinfunction "1_1") (pintype "passive"))
      (node (ref "C21") (pin "1") (pinfunction "1_1") (pintype "passive"))
      (node (ref "L2") (pin "2") (pinfunction "2_2") (pintype "passive"))
      (node (ref "U7") (pin "5") (pinfunction "EN_5") (pintype "input"))
      (node (ref "U7") (pin "8") (pinfunction "IN_8") (pintype "passive"))
    )
    (net (code "56") (name "/V_PROTECT") (class "Default")
      (node (ref "C6") (pin "2") (pinfunction "2_2") (pintype "passive"))
      (node (ref "D1") (pin "C") (pinfunction "C_C") (pintype "passive"))
      (node (ref "D3") (pin "C") (pinfunction "C_C") (pintype "passive"))
      (node (ref "D5") (pin "C") (pinfunction "C_C") (pintype "passive"))
      (node (ref "D7") (pin "C") (pinfunction "C_C") (pintype "passive"))
      (node (ref "D9") (pin "C") (pinfunction "C_C") (pintype "passive"))
      (node (ref "R26") (pin "1") (pinfunction "1_1") (pintype "passive"))
      (node (ref "R27") (pin "1") (pinfunction "1_1") (pintype "passive"))
      (node (ref "TP8") (pin "TP") (pinfunction "TP_TP") (pintype "input"))
    )
    (net (code "57") (name "GND") (class "Default")
      (node (ref "A") (pin "T6") (pinfunction "GND_T6") (pintype "power_in"))
      (node (ref "B") (pin "T6") (pinfunction "GND_T6") (pintype "power_in"))
      (node (ref "C17") (pin "1") (pinfunction "1_1") (pintype "passive"))
      (node (ref "C18") (pin "1") (pinfunction "1_1") (pintype "passive"))
      (node (ref "C19") (pin "2") (pinfunction "2_2") (pintype "passive"))
      (node (ref "C25") (pin "1") (pinfunction "1_1") (pintype "passive"))
      (node (ref "C26") (pin "-") (pinfunction "-_-") (pintype "passive"))
      (node (ref "C27") (pin "1") (pinfunction "1_1") (pintype "passive"))
      (node (ref "C28") (pin "-") (pinfunction "-_-") (pintype "passive"))
      (node (ref "C29") (pin "1") (pinfunction "1_1") (pintype "passive"))
      (node (ref "C30") (pin "1") (pinfunction "1_1") (pintype "passive"))
      (node (ref "C31") (pin "1") (pinfunction "1_1") (pintype "passive"))
      (node (ref "C32") (pin "1") (pinfunction "1_1") (pintype "passive"))
      (node (ref "DI_ISO") (pin "P15") (pinfunction "GND2_P15") (pintype "bidirectional"))
      (node (ref "DI_ISO") (pin "P9") (pinfunction "GND2_P9") (pintype "bidirectional"))
      (node (ref "DO_ISO") (pin "P2") (pinfunction "GND1_P2") (pintype "bidirectional"))
      (node (ref "DO_ISO") (pin "P8") (pinfunction "GND1_P8") (pintype "bidirectional"))
      (node (ref "FMC") (pin "P$102") (pinfunction "P$102_P$102") (pintype "bidirectional"))
      (node (ref "FMC") (pin "P$105") (pinfunction "P$105_P$105") (pintype "bidirectional"))
      (node (ref "FMC") (pin "P$108") (pinfunction "P$108_P$108") (pintype "bidirectional"))
      (node (ref "FMC") (pin "P$117") (pinfunction "P$117_P$117") (pintype "bidirectional"))
      (node (ref "FMC") (pin "P$119") (pinfunction "P$119_P$119") (pintype "bidirectional"))
      (node (ref "FMC") (pin "P$12") (pinfunction "P$12_P$12") (pintype "bidirectional"))
      (node (ref "FMC") (pin "P$121") (pinfunction "P$121_P$121") (pintype "bidirectional"))
      (node (ref "FMC") (pin "P$124") (pinfunction "P$124_P$124") (pintype "bidirectional"))
      (node (ref "FMC") (pin "P$125") (pinfunction "P$125_P$125") (pintype "bidirectional"))
      (node (ref "FMC") (pin "P$128") (pinfunction "P$128_P$128") (pintype "bidirectional"))
      (node (ref "FMC") (pin "P$129") (pinfunction "P$129_P$129") (pintype "bidirectional"))
      (node (ref "FMC") (pin "P$132") (pinfunction "P$132_P$132") (pintype "bidirectional"))
      (node (ref "FMC") (pin "P$133") (pinfunction "P$133_P$133") (pintype "bidirectional"))
      (node (ref "FMC") (pin "P$136") (pinfunction "P$136_P$136") (pintype "bidirectional"))
      (node (ref "FMC") (pin "P$137") (pinfunction "P$137_P$137") (pintype "bidirectional"))
      (node (ref "FMC") (pin "P$140") (pinfunction "P$140_P$140") (pintype "bidirectional"))
      (node (ref "FMC") (pin "P$141") (pinfunction "P$141_P$141") (pintype "bidirectional"))
      (node (ref "FMC") (pin "P$144") (pinfunction "P$144_P$144") (pintype "bidirectional"))
      (node (ref "FMC") (pin "P$145") (pinfunction "P$145_P$145") (pintype "bidirectional"))
      (node (ref "FMC") (pin "P$148") (pinfunction "P$148_P$148") (pintype "bidirectional"))
      (node (ref "FMC") (pin "P$149") (pinfunction "P$149_P$149") (pintype "bidirectional"))
      (node (ref "FMC") (pin "P$15") (pinfunction "P$15_P$15") (pintype "bidirectional"))
      (node (ref "FMC") (pin "P$152") (pinfunction "P$152_P$152") (pintype "bidirectional"))
      (node (ref "FMC") (pin "P$153") (pinfunction "P$153_P$153") (pintype "bidirectional"))
      (node (ref "FMC") (pin "P$156") (pinfunction "P$156_P$156") (pintype "bidirectional"))
      (node (ref "FMC") (pin "P$158") (pinfunction "P$158_P$158") (pintype "bidirectional"))
      (node (ref "FMC") (pin "P$160") (pinfunction "P$160_P$160") (pintype "bidirectional"))
      (node (ref "FMC") (pin "P$18") (pinfunction "P$18_P$18") (pintype "bidirectional"))
      (node (ref "FMC") (pin "P$21") (pinfunction "P$21_P$21") (pintype "bidirectional"))
      (node (ref "FMC") (pin "P$24") (pinfunction "P$24_P$24") (pintype "bidirectional"))
      (node (ref "FMC") (pin "P$27") (pinfunction "P$27_P$27") (pintype "bidirectional"))
      (node (ref "FMC") (pin "P$3") (pinfunction "P$3_P$3") (pintype "bidirectional"))
      (node (ref "FMC") (pin "P$30") (pinfunction "P$30_P$30") (pintype "bidirectional"))
      (node (ref "FMC") (pin "P$33") (pinfunction "P$33_P$33") (pintype "bidirectional"))
      (node (ref "FMC") (pin "P$36") (pinfunction "P$36_P$36") (pintype "bidirectional"))
      (node (ref "FMC") (pin "P$39") (pinfunction "P$39_P$39") (pintype "bidirectional"))
      (node (ref "FMC") (pin "P$41") (pinfunction "P$41_P$41") (pintype "bidirectional"))
      (node (ref "FMC") (pin "P$44") (pinfunction "P$44_P$44") (pintype "bidirectional"))
      (node (ref "FMC") (pin "P$45") (pinfunction "P$45_P$45") (pintype "bidirectional"))
      (node (ref "FMC") (pin "P$48") (pinfunction "P$48_P$48") (pintype "bidirectional"))
      (node (ref "FMC") (pin "P$51") (pinfunction "P$51_P$51") (pintype "bidirectional"))
      (node (ref "FMC") (pin "P$54") (pinfunction "P$54_P$54") (pintype "bidirectional"))
      (node (ref "FMC") (pin "P$57") (pinfunction "P$57_P$57") (pintype "bidirectional"))
      (node (ref "FMC") (pin "P$6") (pinfunction "P$6_P$6") (pintype "bidirectional"))
      (node (ref "FMC") (pin "P$60") (pinfunction "P$60_P$60") (pintype "bidirectional"))
      (node (ref "FMC") (pin "P$63") (pinfunction "P$63_P$63") (pintype "bidirectional"))
      (node (ref "FMC") (pin "P$66") (pinfunction "P$66_P$66") (pintype "bidirectional"))
      (node (ref "FMC") (pin "P$69") (pinfunction "P$69_P$69") (pintype "bidirectional"))
      (node (ref "FMC") (pin "P$72") (pinfunction "P$72_P$72") (pintype "bidirectional"))
      (node (ref "FMC") (pin "P$75") (pinfunction "P$75_P$75") (pintype "bidirectional"))
      (node (ref "FMC") (pin "P$78") (pinfunction "P$78_P$78") (pintype "bidirectional"))
      (node (ref "FMC") (pin "P$80") (pinfunction "P$80_P$80") (pintype "bidirectional"))
      (node (ref "FMC") (pin "P$82") (pinfunction "P$82_P$82") (pintype "bidirectional"))
      (node (ref "FMC") (pin "P$83") (pinfunction "P$83_P$83") (pintype "bidirectional"))
      (node (ref "FMC") (pin "P$86") (pinfunction "P$86_P$86") (pintype "bidirectional"))
      (node (ref "FMC") (pin "P$87") (pinfunction "P$87_P$87") (pintype "bidirectional"))
      (node (ref "FMC") (pin "P$9") (pinfunction "P$9_P$9") (pintype "bidirectional"))
      (node (ref "FMC") (pin "P$90") (pinfunction "P$90_P$90") (pintype "bidirectional"))
      (node (ref "FMC") (pin "P$93") (pinfunction "P$93_P$93") (pintype "bidirectional"))
      (node (ref "FMC") (pin "P$96") (pinfunction "P$96_P$96") (pintype "bidirectional"))
      (node (ref "FMC") (pin "P$99") (pinfunction "P$99_P$99") (pintype "bidirectional"))
      (node (ref "POW_TP") (pin "3") (pinfunction "3_3") (pintype "passive"))
      (node (ref "U6") (pin "P2") (pinfunction "GND_P2") (pintype "bidirectional"))
    )
    (net (code "58") (name "GND_ISO") (class "Default")
      (node (ref "C1") (pin "2") (pinfunction "2_2") (pintype "passive"))
      (node (ref "C10") (pin "2") (pinfunction "2_2") (pintype "passive"))
      (node (ref "C11") (pin "2") (pinfunction "2_2") (pintype "passive"))
      (node (ref "C12") (pin "2") (pinfunction "2_2") (pintype "passive"))
      (node (ref "C13") (pin "2") (pinfunction "2_2") (pintype "passive"))
      (node (ref "C15") (pin "1") (pinfunction "1_1") (pintype "passive"))
      (node (ref "C16") (pin "1") (pinfunction "1_1") (pintype "passive"))
      (node (ref "C20") (pin "2") (pinfunction "2_2") (pintype "passive"))
      (node (ref "C21") (pin "2") (pinfunction "2_2") (pintype "passive"))
      (node (ref "C22") (pin "2") (pinfunction "2_2") (pintype "passive"))
      (node (ref "C24") (pin "2") (pinfunction "2_2") (pintype "passive"))
      (node (ref "C3") (pin "2") (pinfunction "2_2") (pintype "passive"))
      (node (ref "C33") (pin "2") (pinfunction "2_2") (pintype "passive"))
      (node (ref "C34") (pin "2") (pinfunction "2_2") (pintype "passive"))
      (node (ref "C35") (pin "1") (pinfunction "1_1") (pintype "passive"))
      (node (ref "C36") (pin "2") (pinfunction "2_2") (pintype "passive"))
      (node (ref "C37") (pin "2") (pinfunction "2_2") (pintype "passive"))
      (node (ref "C4") (pin "-") (pinfunction "-_-") (pintype "passive"))
      (node (ref "C5") (pin "-") (pinfunction "-_-") (pintype "passive"))
      (node (ref "C6") (pin "1") (pinfunction "1_1") (pintype "passive"))
      (node (ref "C7") (pin "2") (pinfunction "2_2") (pintype "passive"))
      (node (ref "C8") (pin "2") (pinfunction "2_2") (pintype "passive"))
      (node (ref "C9") (pin "2") (pinfunction "2_2") (pintype "passive"))
      (node (ref "C_ISO") (pin "T6") (pinfunction "GND_T6") (pintype "power_in"))
      (node (ref "D2") (pin "A") (pinfunction "A_A") (pintype "passive"))
      (node (ref "D4") (pin "A") (pinfunction "A_A") (pintype "passive"))
      (node (ref "D6") (pin "A") (pinfunction "A_A") (pintype "passive"))
      (node (ref "D8") (pin "A") (pinfunction "A_A") (pintype "passive"))
      (node (ref "D9") (pin "A") (pinfunction "A_A") (pintype "passive"))
      (node (ref "DI0") (pin "GND$1") (pinfunction "2_GND$1") (pintype "passive"))
      (node (ref "DI0") (pin "GND$2") (pinfunction "2_GND$2") (pintype "passive"))
      (node (ref "DI0") (pin "GND$3") (pinfunction "2_GND$3") (pintype "passive"))
      (node (ref "DI0") (pin "GND$4") (pinfunction "2_GND$4") (pintype "passive"))
      (node (ref "DI1") (pin "GND$1") (pinfunction "2_GND$1") (pintype "passive"))
      (node (ref "DI1") (pin "GND$2") (pinfunction "2_GND$2") (pintype "passive"))
      (node (ref "DI1") (pin "GND$3") (pinfunction "2_GND$3") (pintype "passive"))
      (node (ref "DI1") (pin "GND$4") (pinfunction "2_GND$4") (pintype "passive"))
      (node (ref "DI_ISO") (pin "P2") (pinfunction "GND1_P2") (pintype "bidirectional"))
      (node (ref "DI_ISO") (pin "P8") (pinfunction "GND1_P8") (pintype "bidirectional"))
      (node (ref "DO0") (pin "GND$1") (pinfunction "2_GND$1") (pintype "passive"))
      (node (ref "DO0") (pin "GND$2") (pinfunction "2_GND$2") (pintype "passive"))
      (node (ref "DO0") (pin "GND$3") (pinfunction "2_GND$3") (pintype "passive"))
      (node (ref "DO0") (pin "GND$4") (pinfunction "2_GND$4") (pintype "passive"))
      (node (ref "DO1") (pin "GND$1") (pinfunction "2_GND$1") (pintype "passive"))
      (node (ref "DO1") (pin "GND$2") (pinfunction "2_GND$2") (pintype "passive"))
      (node (ref "DO1") (pin "GND$3") (pinfunction "2_GND$3") (pintype "passive"))
      (node (ref "DO1") (pin "GND$4") (pinfunction "2_GND$4") (pintype "passive"))
      (node (ref "DO_ISO") (pin "P15") (pinfunction "GND2_P15") (pintype "bidirectional"))
      (node (ref "DO_ISO") (pin "P9") (pinfunction "GND2_P9") (pintype "bidirectional"))
      (node (ref "IC1") (pin "1") (pinfunction "ADJ_1") (pintype "input"))
      (node (ref "PWR_ISO") (pin "C1") (pinfunction "C_C1") (pintype "passive"))
      (node (ref "PWR_ISO") (pin "C2") (pinfunction "C_C2") (pintype "passive"))
      (node (ref "Q1") (pin "S") (pinfunction "S_S") (pintype "bidirectional"))
      (node (ref "Q2") (pin "S") (pinfunction "S_S") (pintype "bidirectional"))
      (node (ref "R10") (pin "1") (pinfunction "1_1") (pintype "passive"))
      (node (ref "R11") (pin "1") (pinfunction "1_1") (pintype "passive"))
      (node (ref "R13") (pin "2") (pinfunction "2_2") (pintype "passive"))
      (node (ref "R14") (pin "1") (pinfunction "1_1") (pintype "passive"))
      (node (ref "R20") (pin "1") (pinfunction "1_1") (pintype "passive"))
      (node (ref "R21") (pin "1") (pinfunction "1_1") (pintype "passive"))
      (node (ref "R6") (pin "2") (pinfunction "2_2") (pintype "passive"))
      (node (ref "TP1") (pin "TP") (pinfunction "TP_TP") (pintype "input"))
      (node (ref "U$5") (pin "2") (pinfunction "V-_2") (pintype "power_in"))
      (node (ref "U$6") (pin "2") (pinfunction "V-_2") (pintype "power_in"))
      (node (ref "U$7") (pin "7") (pinfunction "GND_7") (pintype "passive"))
      (node (ref "U1") (pin "4") (pinfunction "GND_4") (pintype "passive"))
      (node (ref "U1") (pin "9") (pinfunction "EP_9") (pintype "passive"))
      (node (ref "U3") (pin "4") (pinfunction "GND_4") (pintype "bidirectional"))
      (node (ref "U4") (pin "4") (pinfunction "GND_4") (pintype "bidirectional"))
      (node (ref "U5") (pin "5") (pinfunction "GND_5") (pintype "bidirectional"))
      (node (ref "U6") (pin "P3") (pinfunction "0V_P3") (pintype "bidirectional"))
      (node (ref "U7") (pin "4") (pinfunction "GND_4") (pintype "passive"))
      (node (ref "U7") (pin "9") (pinfunction "EP_9") (pintype "passive"))
    )
    (net (code "59") (name "Net-(C_ISO-MISO1+)") (class "Default")
      (node (ref "C_ISO") (pin "B4") (pinfunction "MISO1+_B4") (pintype "bidirectional"))
      (node (ref "R9") (pin "1") (pinfunction "1_1") (pintype "passive"))
      (node (ref "TP12") (pin "TP") (pinfunction "TP_TP") (pintype "input"))
      (node (ref "U5") (pin "2") (pinfunction "RIN1+_2") (pintype "bidirectional"))
    )
    (net (code "60") (name "Net-(C_ISO-MISO1-)") (class "Default")
      (node (ref "C_ISO") (pin "T4") (pinfunction "MISO1-_T4") (pintype "bidirectional"))
      (node (ref "R9") (pin "2") (pinfunction "2_2") (pintype "passive"))
      (node (ref "TP14") (pin "TP") (pinfunction "TP_TP") (pintype "input"))
      (node (ref "U5") (pin "1") (pinfunction "RIN1-_1") (pintype "bidirectional"))
    )
    (net (code "61") (name "Net-(C_ISO-MISO2+)") (class "Default")
      (node (ref "C_ISO") (pin "B5") (pinfunction "MISO2+_B5") (pintype "bidirectional"))
      (node (ref "R8") (pin "1") (pinfunction "1_1") (pintype "passive"))
      (node (ref "TP9") (pin "TP") (pinfunction "TP_TP") (pintype "input"))
      (node (ref "U5") (pin "3") (pinfunction "RIN2+_3") (pintype "bidirectional"))
    )
    (net (code "62") (name "Net-(C_ISO-MISO2-)") (class "Default")
      (node (ref "C_ISO") (pin "T5") (pinfunction "MISO2-_T5") (pintype "bidirectional"))
      (node (ref "R8") (pin "2") (pinfunction "2_2") (pintype "passive"))
      (node (ref "TP11") (pin "TP") (pinfunction "TP_TP") (pintype "input"))
      (node (ref "U5") (pin "4") (pinfunction "RIN2-_4") (pintype "bidirectional"))
    )
    (net (code "63") (name "Net-(C_ISO-MOSI+)") (class "Default")
      (node (ref "C_ISO") (pin "B3") (pinfunction "MOSI+_B3") (pintype "bidirectional"))
      (node (ref "TP2") (pin "TP") (pinfunction "TP_TP") (pintype "input"))
      (node (ref "U3") (pin "7") (pinfunction "DOUT1+_7") (pintype "bidirectional"))
    )
    (net (code "64") (name "Net-(C_ISO-MOSI-)") (class "Default")
      (node (ref "C_ISO") (pin "T3") (pinfunction "MOSI-_T3") (pintype "bidirectional"))
      (node (ref "TP5") (pin "TP") (pinfunction "TP_TP") (pintype "input"))
      (node (ref "U3") (pin "8") (pinfunction "DOUT1-_8") (pintype "bidirectional"))
    )
    (net (code "65") (name "Net-(C_ISO-SCLK+)") (class "Default")
      (node (ref "C_ISO") (pin "B2") (pinfunction "SCLK+_B2") (pintype "bidirectional"))
      (node (ref "TP3") (pin "TP") (pinfunction "TP_TP") (pintype "input"))
      (node (ref "U3") (pin "6") (pinfunction "DOUT2+_6") (pintype "bidirectional"))
    )
    (net (code "66") (name "Net-(C_ISO-SCLK-)") (class "Default")
      (node (ref "C_ISO") (pin "T2") (pinfunction "SCLK-_T2") (pintype "bidirectional"))
      (node (ref "TP6") (pin "TP") (pinfunction "TP_TP") (pintype "input"))
      (node (ref "U3") (pin "5") (pinfunction "DOUT2-_5") (pintype "bidirectional"))
    )
    (net (code "67") (name "Net-(C_ISO-~{CS}+)") (class "Default")
      (node (ref "C_ISO") (pin "B1") (pinfunction "~{CS}+_B1") (pintype "bidirectional"))
      (node (ref "TP7") (pin "TP") (pinfunction "TP_TP") (pintype "input"))
      (node (ref "U4") (pin "7") (pinfunction "DOUT1+_7") (pintype "bidirectional"))
    )
    (net (code "68") (name "Net-(C_ISO-~{CS}-)") (class "Default")
      (node (ref "C_ISO") (pin "T1") (pinfunction "~{CS}-_T1") (pintype "bidirectional"))
      (node (ref "TP4") (pin "TP") (pinfunction "TP_TP") (pintype "input"))
      (node (ref "U4") (pin "8") (pinfunction "DOUT1-_8") (pintype "bidirectional"))
    )
    (net (code "69") (name "Net-(D1-PadA)") (class "Default")
      (node (ref "D1") (pin "A") (pinfunction "A_A") (pintype "passive"))
      (node (ref "D2") (pin "C") (pinfunction "C_C") (pintype "passive"))
      (node (ref "F2") (pin "2") (pinfunction "2_2") (pintype "passive"))
      (node (ref "R1") (pin "2") (pinfunction "2_2") (pintype "passive"))
      (node (ref "R11") (pin "2") (pinfunction "2_2") (pintype "passive"))
      (node (ref "R15") (pin "1") (pinfunction "1_1") (pintype "passive"))
      (node (ref "R2") (pin "2") (pinfunction "2_2") (pintype "passive"))
      (node (ref "R3") (pin "2") (pinfunction "2_2") (pintype "passive"))
    )
    (net (code "70") (name "Net-(D7-PadA)") (class "Default")
      (node (ref "D7") (pin "A") (pinfunction "A_A") (pintype "passive"))
      (node (ref "D8") (pin "C") (pinfunction "C_C") (pintype "passive"))
      (node (ref "F4") (pin "2") (pinfunction "2_2") (pintype "passive"))
      (node (ref "R17") (pin "2") (pinfunction "2_2") (pintype "passive"))
      (node (ref "R18") (pin "2") (pinfunction "2_2") (pintype "passive"))
      (node (ref "R19") (pin "2") (pinfunction "2_2") (pintype "passive"))
      (node (ref "R20") (pin "2") (pinfunction "2_2") (pintype "passive"))
      (node (ref "R22") (pin "1") (pinfunction "1_1") (pintype "passive"))
    )
    (net (code "71") (name "Net-(DI0-1)") (class "Default")
      (node (ref "DI0") (pin "CLK") (pinfunction "1_CLK") (pintype "passive"))
      (node (ref "F2") (pin "1") (pinfunction "1_1") (pintype "passive"))
    )
    (net (code "72") (name "Net-(DI1-1)") (class "Default")
      (node (ref "DI1") (pin "CLK") (pinfunction "1_CLK") (pintype "passive"))
      (node (ref "F4") (pin "1") (pinfunction "1_1") (pintype "passive"))
    )
    (net (code "73") (name "Net-(DO0-1)") (class "Default")
      (node (ref "DO0") (pin "CLK") (pinfunction "1_CLK") (pintype "passive"))
      (node (ref "F1") (pin "1") (pinfunction "1_1") (pintype "passive"))
    )
    (net (code "74") (name "Net-(DO1-1)") (class "Default")
      (node (ref "DO1") (pin "CLK") (pinfunction "1_CLK") (pintype "passive"))
      (node (ref "F3") (pin "1") (pinfunction "1_1") (pintype "passive"))
    )
    (net (code "75") (name "Net-(IC1-VI)") (class "Default")
      (node (ref "IC1") (pin "3") (pinfunction "VI_3") (pintype "input"))
      (node (ref "L4") (pin "1") (pinfunction "1_1") (pintype "passive"))
    )
    (net (code "76") (name "Net-(PWR_ISOA-A)") (class "Default")
      (node (ref "PWR_ISO") (pin "A1") (pinfunction "A_A1") (pintype "passive"))
      (node (ref "R7") (pin "2") (pinfunction "2_2") (pintype "passive"))
    )
    (net (code "77") (name "Net-(PWR_ISOB-A)") (class "Default")
      (node (ref "PWR_ISO") (pin "A2") (pinfunction "A_A2") (pintype "passive"))
      (node (ref "R4") (pin "2") (pinfunction "2_2") (pintype "passive"))
    )
    (net (code "78") (name "Net-(Q1-PadD)") (class "Default")
      (node (ref "Q1") (pin "D") (pinfunction "D_D") (pintype "bidirectional"))
      (node (ref "R1") (pin "1") (pinfunction "1_1") (pintype "passive"))
      (node (ref "R2") (pin "1") (pinfunction "1_1") (pintype "passive"))
      (node (ref "R3") (pin "1") (pinfunction "1_1") (pintype "passive"))
    )
    (net (code "79") (name "Net-(Q2-PadD)") (class "Default")
      (node (ref "Q2") (pin "D") (pinfunction "D_D") (pintype "bidirectional"))
      (node (ref "R17") (pin "1") (pinfunction "1_1") (pintype "passive"))
      (node (ref "R18") (pin "1") (pinfunction "1_1") (pintype "passive"))
      (node (ref "R19") (pin "1") (pinfunction "1_1") (pintype "passive"))
    )
    (net (code "80") (name "Net-(U$5A-+IN)") (class "Default")
      (node (ref "R15") (pin "2") (pinfunction "2_2") (pintype "passive"))
      (node (ref "U$5") (pin "3") (pinfunction "+IN_3") (pintype "input"))
    )
    (net (code "81") (name "Net-(U$5A--IN)") (class "Default")
      (node (ref "C33") (pin "1") (pinfunction "1_1") (pintype "passive"))
      (node (ref "R16") (pin "2") (pinfunction "2_2") (pintype "passive"))
      (node (ref "U$5") (pin "4") (pinfunction "-IN_4") (pintype "input"))
    )
    (net (code "82") (name "Net-(U$6A-+IN)") (class "Default")
      (node (ref "R22") (pin "2") (pinfunction "2_2") (pintype "passive"))
      (node (ref "U$6") (pin "3") (pinfunction "+IN_3") (pintype "input"))
    )
    (net (code "83") (name "Net-(U$6A--IN)") (class "Default")
      (node (ref "C34") (pin "1") (pinfunction "1_1") (pintype "passive"))
      (node (ref "R23") (pin "2") (pinfunction "2_2") (pintype "passive"))
      (node (ref "U$6") (pin "4") (pinfunction "-IN_4") (pintype "input"))
    )
    (net (code "84") (name "Net-(U$7-1Y)") (class "Default")
      (node (ref "D3") (pin "A") (pinfunction "A_A") (pintype "passive"))
      (node (ref "D4") (pin "C") (pinfunction "C_C") (pintype "passive"))
      (node (ref "F1") (pin "2") (pinfunction "2_2") (pintype "passive"))
      (node (ref "U$7") (pin "3") (pinfunction "1Y_3") (pintype "input"))
      (node (ref "U$7") (pin "6") (pinfunction "2Y_6") (pintype "input"))
    )
    (net (code "85") (name "Net-(U$7-3Y)") (class "Default")
      (node (ref "D5") (pin "A") (pinfunction "A_A") (pintype "passive"))
      (node (ref "D6") (pin "C") (pinfunction "C_C") (pintype "passive"))
      (node (ref "F3") (pin "2") (pinfunction "2_2") (pintype "passive"))
      (node (ref "U$7") (pin "11") (pinfunction "4Y_11") (pintype "passive"))
      (node (ref "U$7") (pin "8") (pinfunction "3Y_8") (pintype "input"))
    )
    (net (code "86") (name "Net-(U$7-~{1G})") (class "Default")
      (node (ref "R24") (pin "1") (pinfunction "1_1") (pintype "passive"))
      (node (ref "U$7") (pin "1") (pinfunction "~{1G}_1") (pintype "input"))
      (node (ref "U$7") (pin "4") (pinfunction "~{2G}_4") (pintype "input"))
    )
    (net (code "87") (name "Net-(U$7-~{3G})") (class "Default")
      (node (ref "R25") (pin "1") (pinfunction "1_1") (pintype "passive"))
      (node (ref "U$7") (pin "10") (pinfunction "~{3G}_10") (pintype "input"))
      (node (ref "U$7") (pin "13") (pinfunction "~{4G}_13") (pintype "input"))
    )
    (net (code "88") (name "Net-(U1-FB)") (class "Default")
      (node (ref "C2") (pin "2") (pinfunction "2_2") (pintype "passive"))
      (node (ref "R5") (pin "2") (pinfunction "2_2") (pintype "passive"))
      (node (ref "R6") (pin "1") (pinfunction "1_1") (pintype "passive"))
      (node (ref "U1") (pin "2") (pinfunction "FB_2") (pintype "input"))
    )
    (net (code "89") (name "Net-(U1-NR{slash}SS)") (class "Default")
      (node (ref "C7") (pin "1") (pinfunction "1_1") (pintype "passive"))
      (node (ref "U1") (pin "6") (pinfunction "NR/SS_6") (pintype "input"))
    )
    (net (code "90") (name "Net-(U4-DIN2)") (class "Default")
      (node (ref "R10") (pin "2") (pinfunction "2_2") (pintype "passive"))
      (node (ref "U4") (pin "3") (pinfunction "DIN2_3") (pintype "bidirectional"))
    )
    (net (code "91") (name "Net-(U6-VIN)") (class "Default")
      (node (ref "L5") (pin "2") (pinfunction "2_2") (pintype "passive"))
      (node (ref "U6") (pin "P1") (pinfunction "VIN_P1") (pintype "bidirectional"))
    )
    (net (code "92") (name "Net-(U7-FB)") (class "Default")
      (node (ref "C23") (pin "2") (pinfunction "2_2") (pintype "passive"))
      (node (ref "R12") (pin "2") (pinfunction "2_2") (pintype "passive"))
      (node (ref "R13") (pin "1") (pinfunction "1_1") (pintype "passive"))
      (node (ref "U7") (pin "2") (pinfunction "FB_2") (pintype "input"))
    )
    (net (code "93") (name "Net-(U7-NR{slash}SS)") (class "Default")
      (node (ref "C22") (pin "1") (pinfunction "1_1") (pintype "passive"))
      (node (ref "U7") (pin "6") (pinfunction "NR/SS_6") (pintype "input"))
    )
    (net (code "94") (name "unconnected-(FMC-PadP$1)") (class "Default")
      (node (ref "FMC") (pin "P$1") (pinfunction "P$1_P$1") (pintype "bidirectional"))
    )
    (net (code "95") (name "unconnected-(FMC-PadP$2)") (class "Default")
      (node (ref "FMC") (pin "P$2") (pinfunction "P$2_P$2") (pintype "bidirectional"))
    )
    (net (code "96") (name "unconnected-(FMC-PadP$4)") (class "Default")
      (node (ref "FMC") (pin "P$4") (pinfunction "P$4_P$4") (pintype "bidirectional"))
    )
    (net (code "97") (name "unconnected-(FMC-PadP$5)") (class "Default")
      (node (ref "FMC") (pin "P$5") (pinfunction "P$5_P$5") (pintype "bidirectional"))
    )
    (net (code "98") (name "unconnected-(FMC-PadP$7)") (class "Default")
      (node (ref "FMC") (pin "P$7") (pinfunction "P$7_P$7") (pintype "bidirectional"))
    )
    (net (code "99") (name "unconnected-(FMC-PadP$8)") (class "Default")
      (node (ref "FMC") (pin "P$8") (pinfunction "P$8_P$8") (pintype "bidirectional"))
    )
    (net (code "100") (name "unconnected-(FMC-PadP$10)") (class "Default")
      (node (ref "FMC") (pin "P$10") (pinfunction "P$10_P$10") (pintype "bidirectional"))
    )
    (net (code "101") (name "unconnected-(FMC-PadP$11)") (class "Default")
      (node (ref "FMC") (pin "P$11") (pinfunction "P$11_P$11") (pintype "bidirectional"))
    )
    (net (code "102") (name "unconnected-(FMC-PadP$40)") (class "Default")
      (node (ref "FMC") (pin "P$40") (pinfunction "P$40_P$40") (pintype "bidirectional"))
    )
    (net (code "103") (name "unconnected-(FMC-PadP$42)") (class "Default")
      (node (ref "FMC") (pin "P$42") (pinfunction "P$42_P$42") (pintype "bidirectional"))
    )
    (net (code "104") (name "unconnected-(FMC-PadP$43)") (class "Default")
      (node (ref "FMC") (pin "P$43") (pinfunction "P$43_P$43") (pintype "bidirectional"))
    )
    (net (code "105") (name "unconnected-(FMC-PadP$46)") (class "Default")
      (node (ref "FMC") (pin "P$46") (pinfunction "P$46_P$46") (pintype "bidirectional"))
    )
    (net (code "106") (name "unconnected-(FMC-PadP$47)") (class "Default")
      (node (ref "FMC") (pin "P$47") (pinfunction "P$47_P$47") (pintype "bidirectional"))
    )
    (net (code "107") (name "unconnected-(FMC-PadP$68)") (class "Default")
      (node (ref "FMC") (pin "P$68") (pinfunction "P$68_P$68") (pintype "bidirectional"))
    )
    (net (code "108") (name "unconnected-(FMC-PadP$70)") (class "Default")
      (node (ref "FMC") (pin "P$70") (pinfunction "P$70_P$70") (pintype "bidirectional"))
    )
    (net (code "109") (name "unconnected-(FMC-PadP$71)") (class "Default")
      (node (ref "FMC") (pin "P$71") (pinfunction "P$71_P$71") (pintype "bidirectional"))
    )
    (net (code "110") (name "unconnected-(FMC-PadP$73)") (class "Default")
      (node (ref "FMC") (pin "P$73") (pinfunction "P$73_P$73") (pintype "bidirectional"))
    )
    (net (code "111") (name "unconnected-(FMC-PadP$74)") (class "Default")
      (node (ref "FMC") (pin "P$74") (pinfunction "P$74_P$74") (pintype "bidirectional"))
    )
    (net (code "112") (name "unconnected-(FMC-PadP$76)") (class "Default")
      (node (ref "FMC") (pin "P$76") (pinfunction "P$76_P$76") (pintype "bidirectional"))
    )
    (net (code "113") (name "unconnected-(FMC-PadP$77)") (class "Default")
      (node (ref "FMC") (pin "P$77") (pinfunction "P$77_P$77") (pintype "bidirectional"))
    )
    (net (code "114") (name "unconnected-(FMC-PadP$79)") (class "Default")
      (node (ref "FMC") (pin "P$79") (pinfunction "P$79_P$79") (pintype "bidirectional"))
    )
    (net (code "115") (name "unconnected-(FMC-PadP$81)") (class "Default")
      (node (ref "FMC") (pin "P$81") (pinfunction "P$81_P$81") (pintype "bidirectional"))
    )
    (net (code "116") (name "unconnected-(FMC-PadP$84)") (class "Default")
      (node (ref "FMC") (pin "P$84") (pinfunction "P$84_P$84") (pintype "bidirectional"))
    )
    (net (code "117") (name "unconnected-(FMC-PadP$85)") (class "Default")
      (node (ref "FMC") (pin "P$85") (pinfunction "P$85_P$85") (pintype "bidirectional"))
    )
    (net (code "118") (name "unconnected-(FMC-PadP$88)") (class "Default")
      (node (ref "FMC") (pin "P$88") (pinfunction "P$88_P$88") (pintype "bidirectional"))
    )
    (net (code "119") (name "unconnected-(FMC-PadP$89)") (class "Default")
      (node (ref "FMC") (pin "P$89") (pinfunction "P$89_P$89") (pintype "bidirectional"))
    )
    (net (code "120") (name "unconnected-(FMC-PadP$91)") (class "Default")
      (node (ref "FMC") (pin "P$91") (pinfunction "P$91_P$91") (pintype "bidirectional"))
    )
    (net (code "121") (name "unconnected-(FMC-PadP$92)") (class "Default")
      (node (ref "FMC") (pin "P$92") (pinfunction "P$92_P$92") (pintype "bidirectional"))
    )
    (net (code "122") (name "unconnected-(FMC-PadP$94)") (class "Default")
      (node (ref "FMC") (pin "P$94") (pinfunction "P$94_P$94") (pintype "bidirectional"))
    )
    (net (code "123") (name "unconnected-(FMC-PadP$95)") (class "Default")
      (node (ref "FMC") (pin "P$95") (pinfunction "P$95_P$95") (pintype "bidirectional"))
    )
    (net (code "124") (name "unconnected-(FMC-PadP$97)") (class "Default")
      (node (ref "FMC") (pin "P$97") (pinfunction "P$97_P$97") (pintype "bidirectional"))
    )
    (net (code "125") (name "unconnected-(FMC-PadP$98)") (class "Default")
      (node (ref "FMC") (pin "P$98") (pinfunction "P$98_P$98") (pintype "bidirectional"))
    )
    (net (code "126") (name "unconnected-(FMC-PadP$100)") (class "Default")
      (node (ref "FMC") (pin "P$100") (pinfunction "P$100_P$100") (pintype "bidirectional"))
    )
    (net (code "127") (name "unconnected-(FMC-PadP$101)") (class "Default")
      (node (ref "FMC") (pin "P$101") (pinfunction "P$101_P$101") (pintype "bidirectional"))
    )
    (net (code "128") (name "unconnected-(FMC-PadP$103)") (class "Default")
      (node (ref "FMC") (pin "P$103") (pinfunction "P$103_P$103") (pintype "bidirectional"))
    )
    (net (code "129") (name "unconnected-(FMC-PadP$104)") (class "Default")
      (node (ref "FMC") (pin "P$104") (pinfunction "P$104_P$104") (pintype "bidirectional"))
    )
    (net (code "130") (name "unconnected-(FMC-PadP$106)") (class "Default")
      (node (ref "FMC") (pin "P$106") (pinfunction "P$106_P$106") (pintype "bidirectional"))
    )
    (net (code "131") (name "unconnected-(FMC-PadP$107)") (class "Default")
      (node (ref "FMC") (pin "P$107") (pinfunction "P$107_P$107") (pintype "bidirectional"))
    )
    (net (code "132") (name "unconnected-(FMC-PadP$109)") (class "Default")
      (node (ref "FMC") (pin "P$109") (pinfunction "P$109_P$109") (pintype "bidirectional"))
    )
    (net (code "133") (name "unconnected-(FMC-PadP$112)") (class "Default")
      (node (ref "FMC") (pin "P$112") (pinfunction "P$112_P$112") (pintype "bidirectional"))
    )
    (net (code "134") (name "unconnected-(FMC-PadP$113)") (class "Default")
      (node (ref "FMC") (pin "P$113") (pinfunction "P$113_P$113") (pintype "bidirectional"))
    )
    (net (code "135") (name "unconnected-(FMC-PadP$114)") (class "Default")
      (node (ref "FMC") (pin "P$114") (pinfunction "P$114_P$114") (pintype "bidirectional"))
    )
    (net (code "136") (name "unconnected-(FMC-PadP$115)") (class "Default")
      (node (ref "FMC") (pin "P$115") (pinfunction "P$115_P$115") (pintype "bidirectional"))
    )
    (net (code "137") (name "unconnected-(FMC-PadP$122)") (class "Default")
      (node (ref "FMC") (pin "P$122") (pinfunction "P$122_P$122") (pintype "bidirectional"))
    )
    (net (code "138") (name "unconnected-(FMC-PadP$123)") (class "Default")
      (node (ref "FMC") (pin "P$123") (pinfunction "P$123_P$123") (pintype "bidirectional"))
    )
    (net (code "139") (name "unconnected-(FMC-PadP$126)") (class "Default")
      (node (ref "FMC") (pin "P$126") (pinfunction "P$126_P$126") (pintype "bidirectional"))
    )
    (net (code "140") (name "unconnected-(FMC-PadP$127)") (class "Default")
      (node (ref "FMC") (pin "P$127") (pinfunction "P$127_P$127") (pintype "bidirectional"))
    )
    (net (code "141") (name "unconnected-(FMC-PadP$130)") (class "Default")
      (node (ref "FMC") (pin "P$130") (pinfunction "P$130_P$130") (pintype "bidirectional"))
    )
    (net (code "142") (name "unconnected-(FMC-PadP$131)") (class "Default")
      (node (ref "FMC") (pin "P$131") (pinfunction "P$131_P$131") (pintype "bidirectional"))
    )
    (net (code "143") (name "unconnected-(FMC-PadP$134)") (class "Default")
      (node (ref "FMC") (pin "P$134") (pinfunction "P$134_P$134") (pintype "bidirectional"))
    )
    (net (code "144") (name "unconnected-(FMC-PadP$135)") (class "Default")
      (node (ref "FMC") (pin "P$135") (pinfunction "P$135_P$135") (pintype "bidirectional"))
    )
    (net (code "145") (name "unconnected-(FMC-PadP$138)") (class "Default")
      (node (ref "FMC") (pin "P$138") (pinfunction "P$138_P$138") (pintype "bidirectional"))
    )
    (net (code "146") (name "unconnected-(FMC-PadP$139)") (class "Default")
      (node (ref "FMC") (pin "P$139") (pinfunction "P$139_P$139") (pintype "bidirectional"))
    )
    (net (code "147") (name "unconnected-(FMC-PadP$142)") (class "Default")
      (node (ref "FMC") (pin "P$142") (pinfunction "P$142_P$142") (pintype "bidirectional"))
    )
    (net (code "148") (name "unconnected-(FMC-PadP$143)") (class "Default")
      (node (ref "FMC") (pin "P$143") (pinfunction "P$143_P$143") (pintype "bidirectional"))
    )
    (net (code "149") (name "unconnected-(FMC-PadP$146)") (class "Default")
      (node (ref "FMC") (pin "P$146") (pinfunction "P$146_P$146") (pintype "bidirectional"))
    )
    (net (code "150") (name "unconnected-(FMC-PadP$147)") (class "Default")
      (node (ref "FMC") (pin "P$147") (pinfunction "P$147_P$147") (pintype "bidirectional"))
    )
    (net (code "151") (name "unconnected-(FMC-PadP$150)") (class "Default")
      (node (ref "FMC") (pin "P$150") (pinfunction "P$150_P$150") (pintype "bidirectional"))
    )
    (net (code "152") (name "unconnected-(FMC-PadP$151)") (class "Default")
      (node (ref "FMC") (pin "P$151") (pinfunction "P$151_P$151") (pintype "bidirectional"))
    )
    (net (code "153") (name "unconnected-(FMC-PadP$154)") (class "Default")
      (node (ref "FMC") (pin "P$154") (pinfunction "P$154_P$154") (pintype "bidirectional"))
    )
    (net (code "154") (name "unconnected-(POW_TP-Pad2)") (class "Default")
      (node (ref "POW_TP") (pin "2") (pinfunction "2_2") (pintype "passive"))
    )
    (net (code "155") (name "unconnected-(U1-DNC-Pad7)") (class "Default")
      (node (ref "U1") (pin "7") (pinfunction "DNC_7") (pintype "no_connect"))
    )
    (net (code "156") (name "unconnected-(U1-NC-Pad3)") (class "Default")
      (node (ref "U1") (pin "3") (pinfunction "NC_3") (pintype "no_connect"))
    )
    (net (code "157") (name "unconnected-(U4-DOUT2+-Pad6)") (class "Default")
      (node (ref "U4") (pin "6") (pinfunction "DOUT2+_6") (pintype "bidirectional"))
    )
    (net (code "158") (name "unconnected-(U4-DOUT2--Pad5)") (class "Default")
      (node (ref "U4") (pin "5") (pinfunction "DOUT2-_5") (pintype "bidirectional"))
    )
    (net (code "159") (name "unconnected-(U7-DNC-Pad7)") (class "Default")
      (node (ref "U7") (pin "7") (pinfunction "DNC_7") (pintype "no_connect"))
    )
    (net (code "160") (name "unconnected-(U7-NC-Pad3)") (class "Default")
      (node (ref "U7") (pin "3") (pinfunction "NC_3") (pintype "no_connect"))
    )
  )
)
